# PCB_TrafficLight_-_Copy.net
KiCad netlist of a schematic drawn in Altium Designer
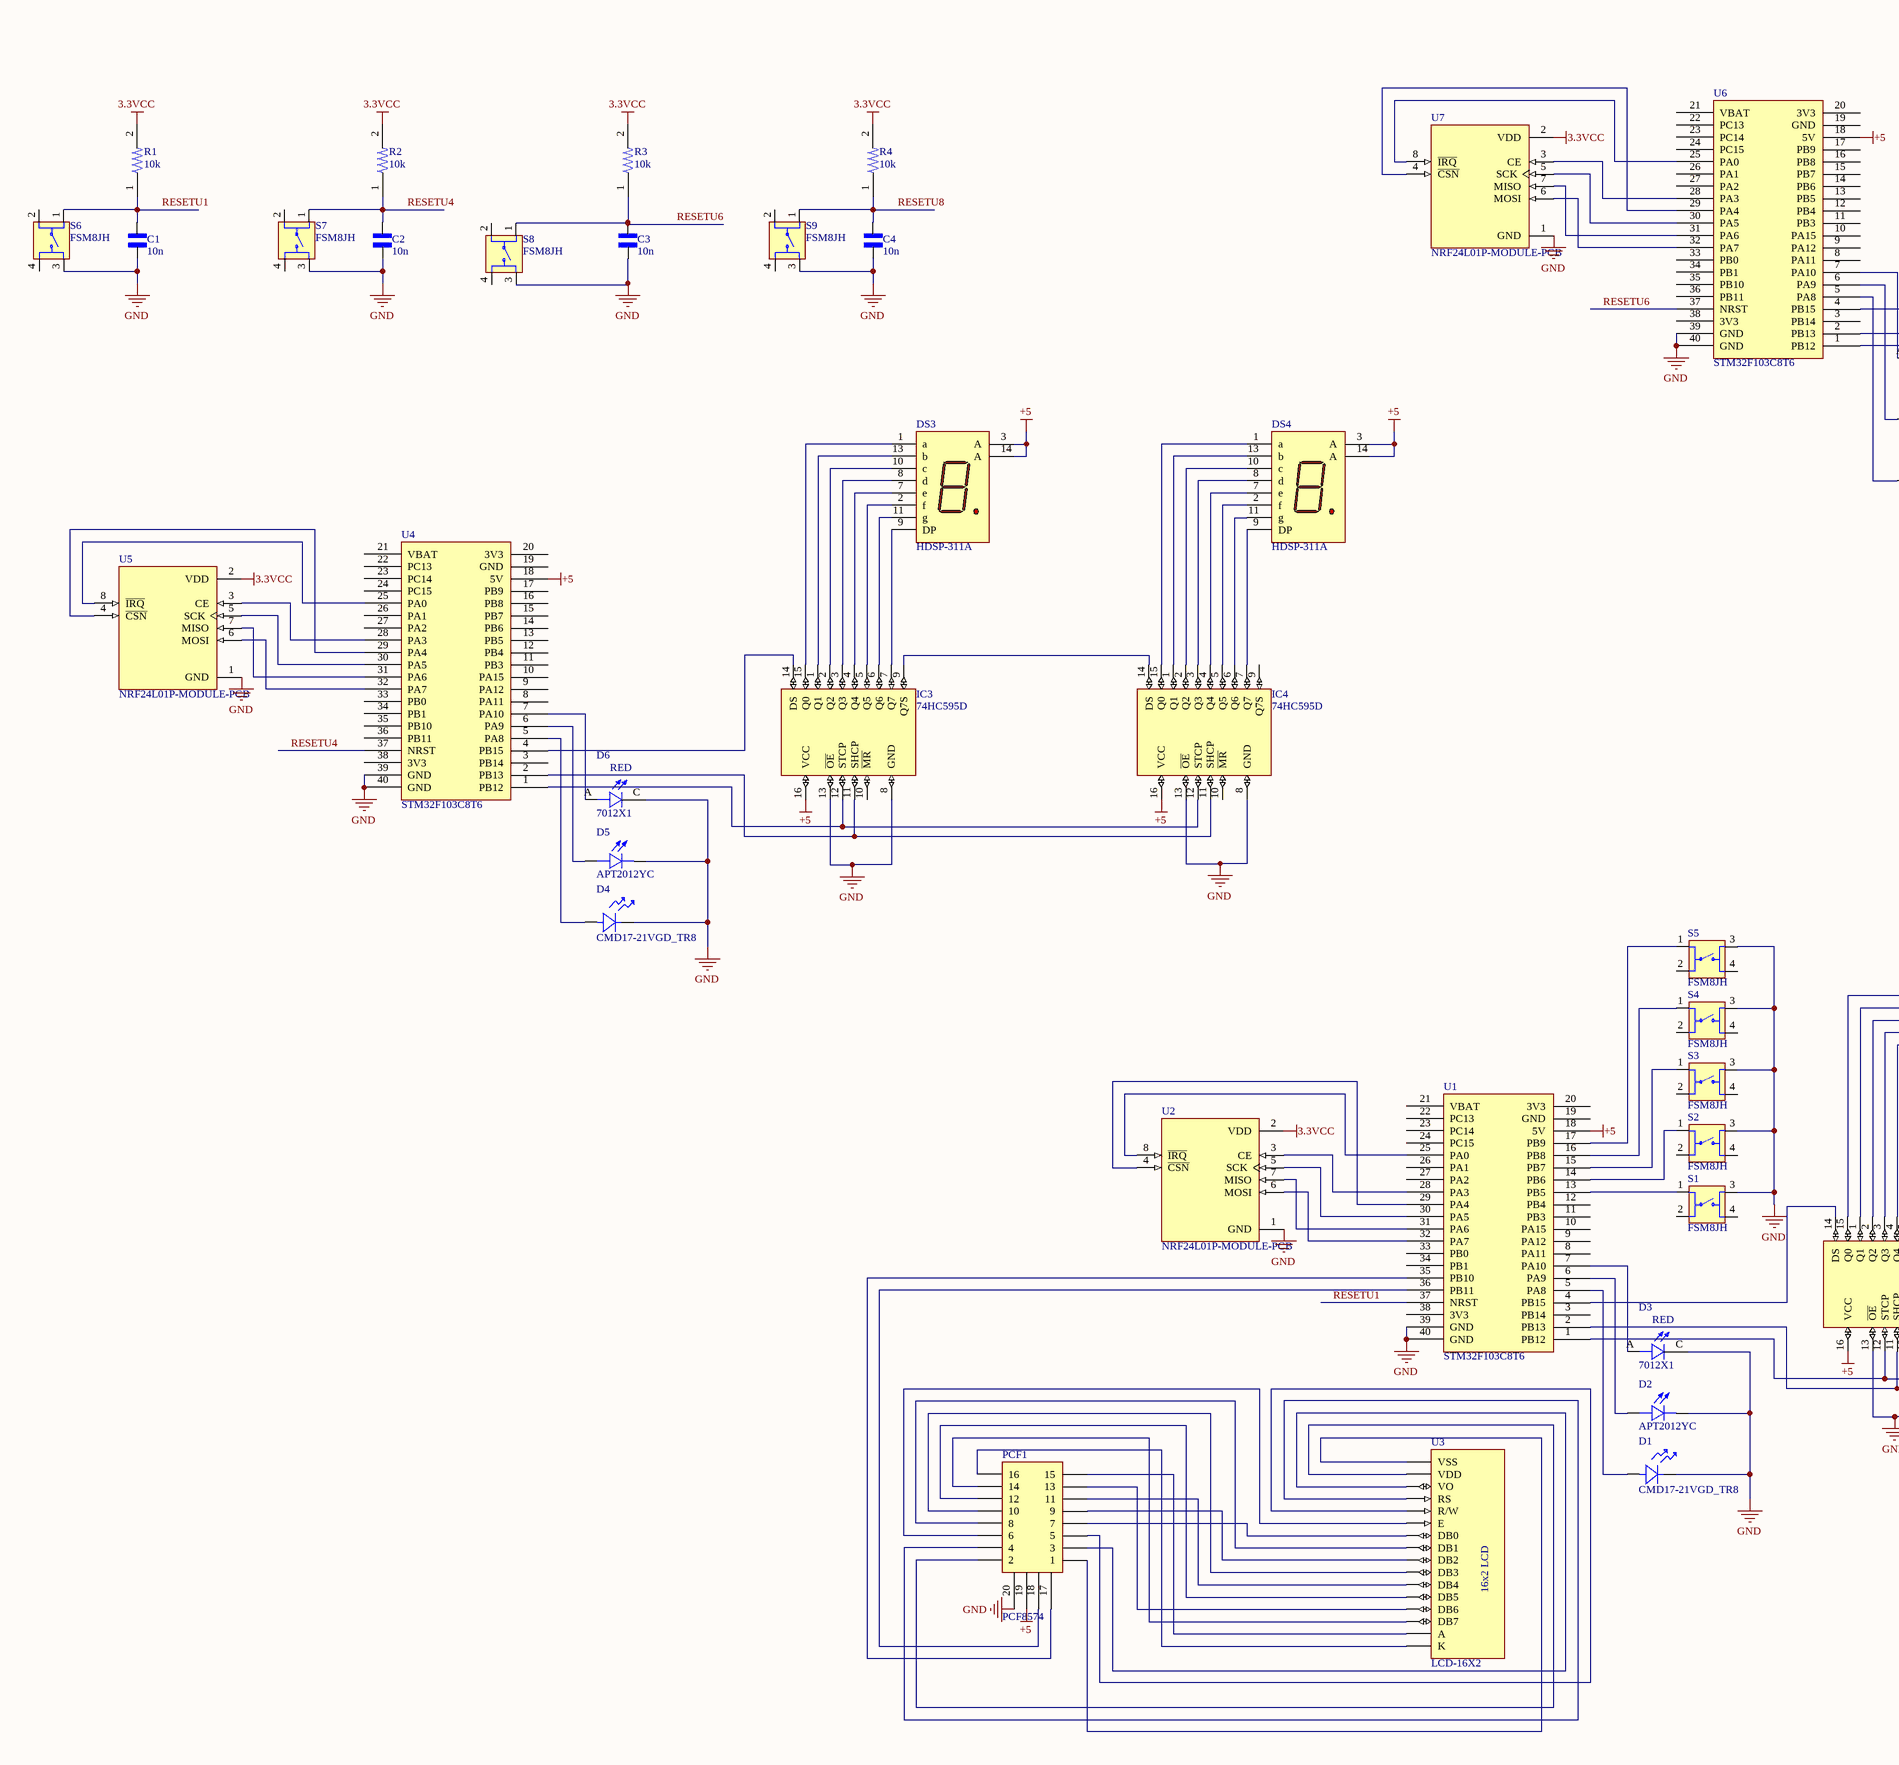
[diagram p0: PCB_TrafficLight - Copy.SchDoc, left]
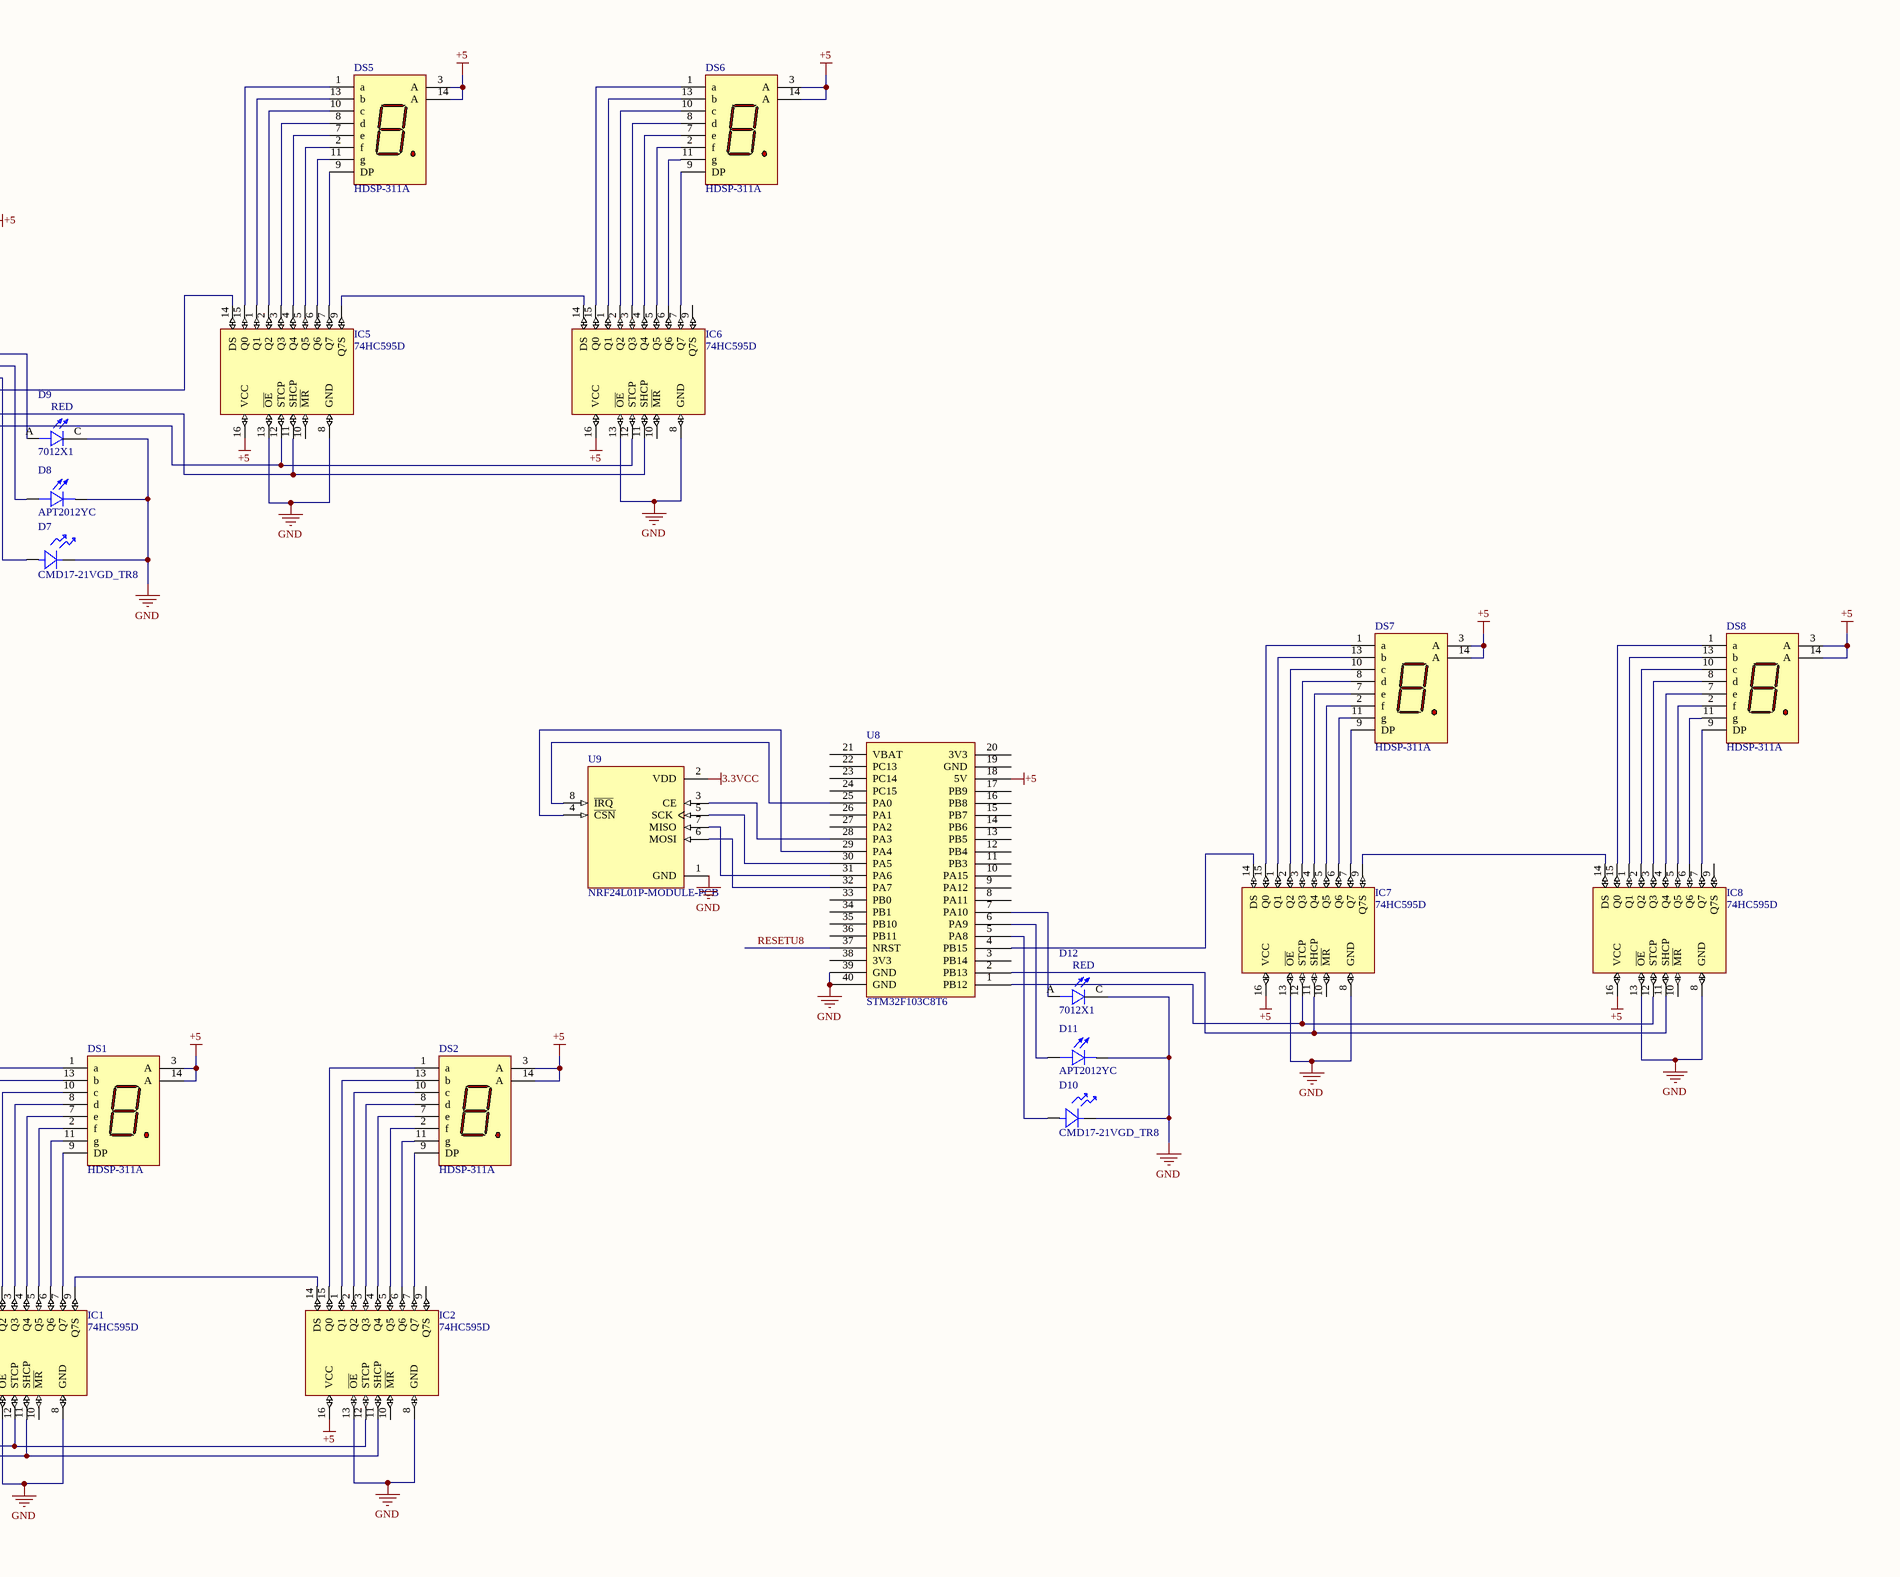
[diagram p1: PCB_TrafficLight - Copy.SchDoc, right]

(export (version "E")
  (design (tool "Eeschema 10.0.6"))
  (components
    (comp (ref "C1")
      (value "10n")
      (footprint "CAPC1005X55N")
      (description "Multilayer Ceramic Capacitors MLCC - SMD/SMT")
      (fields (field (name "MF") "Murata") (field (name "MP") "GCM155R11H103KA40D"))
      (libsource (lib "GCM155R11H103KA40D") (part "GCM155R11H103KA40D"))
    )
    (comp (ref "C2")
      (value "10n")
      (footprint "CAPC1005X55N")
      (description "Multilayer Ceramic Capacitors MLCC - SMD/SMT")
      (fields (field (name "MF") "Murata") (field (name "MP") "GCM155R11H103KA40D"))
      (libsource (lib "GCM155R11H103KA40D") (part "GCM155R11H103KA40D"))
    )
    (comp (ref "C3")
      (value "10n")
      (footprint "CAPC1005X55N")
      (description "Multilayer Ceramic Capacitors MLCC - SMD/SMT")
      (fields (field (name "MF") "Murata") (field (name "MP") "GCM155R11H103KA40D"))
      (libsource (lib "GCM155R11H103KA40D") (part "GCM155R11H103KA40D"))
    )
    (comp (ref "C4")
      (value "10n")
      (footprint "CAPC1005X55N")
      (description "Multilayer Ceramic Capacitors MLCC - SMD/SMT")
      (fields (field (name "MF") "Murata") (field (name "MP") "GCM155R11H103KA40D"))
      (libsource (lib "GCM155R11H103KA40D") (part "GCM155R11H103KA40D"))
    )
    (comp (ref "D1")
      (value "CMD17-21VGD_TR8")
      (footprint "LED_CMD17-21VGD_TR8")
      (description "Green - LED Indication - Discrete 2.1V 0805 (2012 Metric)")
      (fields (field (name "MF") "VCC") (field (name "MP") "CMD17-21VGD/TR8"))
      (libsource (lib "CMD17-21VGD_TR8") (part "CMD17-21VGD_TR8"))
    )
    (comp (ref "D2")
      (value "APT2012YC")
      (footprint "LED_APT2012YC")
      (fields (field (name "MF") "{'manufacturer': u'Kingbright'}"))
      (libsource (lib "APT2012YC") (part "APT2012YC"))
    )
    (comp (ref "D3")
      (value "7012X1")
      (footprint "LED_7012X1")
      (description "Red - LED Indication - Discrete 1.7V 0805 (2012 Metric)")
      (fields (field (name "MF") "VCC"))
      (libsource (lib "7012X1") (part "7012X1"))
    )
    (comp (ref "D4")
      (value "CMD17-21VGD_TR8")
      (footprint "LED_CMD17-21VGD_TR8")
      (description "Green - LED Indication - Discrete 2.1V 0805 (2012 Metric)")
      (fields (field (name "MF") "VCC") (field (name "MP") "CMD17-21VGD/TR8"))
      (libsource (lib "CMD17-21VGD_TR8") (part "CMD17-21VGD_TR8"))
    )
    (comp (ref "D5")
      (value "APT2012YC")
      (footprint "LED_APT2012YC")
      (fields (field (name "MF") "{'manufacturer': u'Kingbright'}"))
      (libsource (lib "APT2012YC") (part "APT2012YC"))
    )
    (comp (ref "D6")
      (value "7012X1")
      (footprint "LED_7012X1")
      (description "Red - LED Indication - Discrete 1.7V 0805 (2012 Metric)")
      (fields (field (name "MF") "VCC"))
      (libsource (lib "7012X1") (part "7012X1"))
    )
    (comp (ref "D7")
      (value "CMD17-21VGD_TR8")
      (footprint "LED_CMD17-21VGD_TR8")
      (description "Green - LED Indication - Discrete 2.1V 0805 (2012 Metric)")
      (fields (field (name "MF") "VCC") (field (name "MP") "CMD17-21VGD/TR8"))
      (libsource (lib "CMD17-21VGD_TR8") (part "CMD17-21VGD_TR8"))
    )
    (comp (ref "D8")
      (value "APT2012YC")
      (footprint "LED_APT2012YC")
      (fields (field (name "MF") "{'manufacturer': u'Kingbright'}"))
      (libsource (lib "APT2012YC") (part "APT2012YC"))
    )
    (comp (ref "D9")
      (value "7012X1")
      (footprint "LED_7012X1")
      (description "Red - LED Indication - Discrete 1.7V 0805 (2012 Metric)")
      (fields (field (name "MF") "VCC"))
      (libsource (lib "7012X1") (part "7012X1"))
    )
    (comp (ref "D10")
      (value "CMD17-21VGD_TR8")
      (footprint "LED_CMD17-21VGD_TR8")
      (description "Green - LED Indication - Discrete 2.1V 0805 (2012 Metric)")
      (fields (field (name "MF") "VCC") (field (name "MP") "CMD17-21VGD/TR8"))
      (libsource (lib "CMD17-21VGD_TR8") (part "CMD17-21VGD_TR8"))
    )
    (comp (ref "D11")
      (value "APT2012YC")
      (footprint "LED_APT2012YC")
      (fields (field (name "MF") "{'manufacturer': u'Kingbright'}"))
      (libsource (lib "APT2012YC") (part "APT2012YC"))
    )
    (comp (ref "D12")
      (value "7012X1")
      (footprint "LED_7012X1")
      (description "Red - LED Indication - Discrete 1.7V 0805 (2012 Metric)")
      (fields (field (name "MF") "VCC"))
      (libsource (lib "7012X1") (part "7012X1"))
    )
    (comp (ref "DS1")
      (value "HDSP-311A")
      (footprint "F-10(14)")
      (description "10.16 mm Single Digit General Purpose AlGaAs Red 7-Segment Display: CA, RH DP")
      (fields (field (name "PUBLISHER") "Altium Limited"))
      (libsource (lib "Agilent LED Display 7-Segment, 1-Digit") (part "HDSP-311A"))
    )
    (comp (ref "DS2")
      (value "HDSP-311A")
      (footprint "F-10(14)")
      (description "10.16 mm Single Digit General Purpose AlGaAs Red 7-Segment Display: CA, RH DP")
      (fields (field (name "PUBLISHER") "Altium Limited"))
      (libsource (lib "Agilent LED Display 7-Segment, 1-Digit") (part "HDSP-311A"))
    )
    (comp (ref "DS3")
      (value "HDSP-311A")
      (footprint "F-10(14)")
      (description "10.16 mm Single Digit General Purpose AlGaAs Red 7-Segment Display: CA, RH DP")
      (fields (field (name "PUBLISHER") "Altium Limited"))
      (libsource (lib "Agilent LED Display 7-Segment, 1-Digit") (part "HDSP-311A"))
    )
    (comp (ref "DS4")
      (value "HDSP-311A")
      (footprint "F-10(14)")
      (description "10.16 mm Single Digit General Purpose AlGaAs Red 7-Segment Display: CA, RH DP")
      (fields (field (name "PUBLISHER") "Altium Limited"))
      (libsource (lib "Agilent LED Display 7-Segment, 1-Digit") (part "HDSP-311A"))
    )
    (comp (ref "DS5")
      (value "HDSP-311A")
      (footprint "F-10(14)")
      (description "10.16 mm Single Digit General Purpose AlGaAs Red 7-Segment Display: CA, RH DP")
      (fields (field (name "PUBLISHER") "Altium Limited"))
      (libsource (lib "Agilent LED Display 7-Segment, 1-Digit") (part "HDSP-311A"))
    )
    (comp (ref "DS6")
      (value "HDSP-311A")
      (footprint "F-10(14)")
      (description "10.16 mm Single Digit General Purpose AlGaAs Red 7-Segment Display: CA, RH DP")
      (fields (field (name "PUBLISHER") "Altium Limited"))
      (libsource (lib "Agilent LED Display 7-Segment, 1-Digit") (part "HDSP-311A"))
    )
    (comp (ref "DS7")
      (value "HDSP-311A")
      (footprint "F-10(14)")
      (description "10.16 mm Single Digit General Purpose AlGaAs Red 7-Segment Display: CA, RH DP")
      (fields (field (name "PUBLISHER") "Altium Limited"))
      (libsource (lib "Agilent LED Display 7-Segment, 1-Digit") (part "HDSP-311A"))
    )
    (comp (ref "DS8")
      (value "HDSP-311A")
      (footprint "F-10(14)")
      (description "10.16 mm Single Digit General Purpose AlGaAs Red 7-Segment Display: CA, RH DP")
      (fields (field (name "PUBLISHER") "Altium Limited"))
      (libsource (lib "Agilent LED Display 7-Segment, 1-Digit") (part "HDSP-311A"))
    )
    (comp (ref "IC1")
      (value "74HC595D")
      (footprint "SOIC127P600X175-16N")
      (description "Shift Register Single 8-Bit Serial to Serial/Parallel 16-Pin SOIC T/R")
      (fields (field (name "MF") "NXP Semiconductors"))
      (libsource (lib "74HC595D") (part "74HC595D"))
    )
    (comp (ref "IC2")
      (value "74HC595D")
      (footprint "SOIC127P600X175-16N")
      (description "Shift Register Single 8-Bit Serial to Serial/Parallel 16-Pin SOIC T/R")
      (fields (field (name "MF") "NXP Semiconductors"))
      (libsource (lib "74HC595D") (part "74HC595D"))
    )
    (comp (ref "IC3")
      (value "74HC595D")
      (footprint "SOIC127P600X175-16N")
      (description "Shift Register Single 8-Bit Serial to Serial/Parallel 16-Pin SOIC T/R")
      (fields (field (name "MF") "NXP Semiconductors"))
      (libsource (lib "74HC595D") (part "74HC595D"))
    )
    (comp (ref "IC4")
      (value "74HC595D")
      (footprint "SOIC127P600X175-16N")
      (description "Shift Register Single 8-Bit Serial to Serial/Parallel 16-Pin SOIC T/R")
      (fields (field (name "MF") "NXP Semiconductors"))
      (libsource (lib "74HC595D") (part "74HC595D"))
    )
    (comp (ref "IC5")
      (value "74HC595D")
      (footprint "SOIC127P600X175-16N")
      (description "Shift Register Single 8-Bit Serial to Serial/Parallel 16-Pin SOIC T/R")
      (fields (field (name "MF") "NXP Semiconductors"))
      (libsource (lib "74HC595D") (part "74HC595D"))
    )
    (comp (ref "IC6")
      (value "74HC595D")
      (footprint "SOIC127P600X175-16N")
      (description "Shift Register Single 8-Bit Serial to Serial/Parallel 16-Pin SOIC T/R")
      (fields (field (name "MF") "NXP Semiconductors"))
      (libsource (lib "74HC595D") (part "74HC595D"))
    )
    (comp (ref "IC7")
      (value "74HC595D")
      (footprint "SOIC127P600X175-16N")
      (description "Shift Register Single 8-Bit Serial to Serial/Parallel 16-Pin SOIC T/R")
      (fields (field (name "MF") "NXP Semiconductors"))
      (libsource (lib "74HC595D") (part "74HC595D"))
    )
    (comp (ref "IC8")
      (value "74HC595D")
      (footprint "SOIC127P600X175-16N")
      (description "Shift Register Single 8-Bit Serial to Serial/Parallel 16-Pin SOIC T/R")
      (fields (field (name "MF") "NXP Semiconductors"))
      (libsource (lib "74HC595D") (part "74HC595D"))
    )
    (comp (ref "PCF1") (value "PCF8574") (footprint "PCF8574") (libsource (lib "PCF8574") (part "PCF8574")))
    (comp (ref "R1")
      (value "10k")
      (footprint "RESC1608X50N_CPF0603F10KC1")
      (description "Res Thin Film 0603 10K Ohm 1% 1/16W Â±50ppm/Â°C Molded SMD SMD Paper T/R")
      (fields (field (name "TOLERANCE") "1%") (field (name "MF") "TE Connectivity"))
      (libsource (lib "CPF0603F10KC1") (part "CPF0603F10KC1"))
    )
    (comp (ref "R2")
      (value "10k")
      (footprint "RESC1608X50N_CPF0603F10KC1")
      (description "Res Thin Film 0603 10K Ohm 1% 1/16W Â±50ppm/Â°C Molded SMD SMD Paper T/R")
      (fields (field (name "TOLERANCE") "1%") (field (name "MF") "TE Connectivity"))
      (libsource (lib "CPF0603F10KC1") (part "CPF0603F10KC1"))
    )
    (comp (ref "R3")
      (value "10k")
      (footprint "RESC1608X50N_CPF0603F10KC1")
      (description "Res Thin Film 0603 10K Ohm 1% 1/16W Â±50ppm/Â°C Molded SMD SMD Paper T/R")
      (fields (field (name "TOLERANCE") "1%") (field (name "MF") "TE Connectivity"))
      (libsource (lib "CPF0603F10KC1") (part "CPF0603F10KC1"))
    )
    (comp (ref "R4")
      (value "10k")
      (footprint "RESC1608X50N_CPF0603F10KC1")
      (description "Res Thin Film 0603 10K Ohm 1% 1/16W Â±50ppm/Â°C Molded SMD SMD Paper T/R")
      (fields (field (name "TOLERANCE") "1%") (field (name "MF") "TE Connectivity"))
      (libsource (lib "CPF0603F10KC1") (part "CPF0603F10KC1"))
    )
    (comp (ref "S1")
      (value "FSM8JH")
      (footprint "SW_FSM8JH")
      (description "Tactile Switch SPST-NO Top Actuated Through Hole")
      (fields (field (name "MF") "TE Connectivity"))
      (libsource (lib "FSM8JH") (part "FSM8JH"))
    )
    (comp (ref "S2")
      (value "FSM8JH")
      (footprint "SW_FSM8JH")
      (description "Tactile Switch SPST-NO Top Actuated Through Hole")
      (fields (field (name "MF") "TE Connectivity"))
      (libsource (lib "FSM8JH") (part "FSM8JH"))
    )
    (comp (ref "S3")
      (value "FSM8JH")
      (footprint "SW_FSM8JH")
      (description "Tactile Switch SPST-NO Top Actuated Through Hole")
      (fields (field (name "MF") "TE Connectivity"))
      (libsource (lib "FSM8JH") (part "FSM8JH"))
    )
    (comp (ref "S4")
      (value "FSM8JH")
      (footprint "SW_FSM8JH")
      (description "Tactile Switch SPST-NO Top Actuated Through Hole")
      (fields (field (name "MF") "TE Connectivity"))
      (libsource (lib "FSM8JH") (part "FSM8JH"))
    )
    (comp (ref "S5")
      (value "FSM8JH")
      (footprint "SW_FSM8JH")
      (description "Tactile Switch SPST-NO Top Actuated Through Hole")
      (fields (field (name "MF") "TE Connectivity"))
      (libsource (lib "FSM8JH") (part "FSM8JH"))
    )
    (comp (ref "S6")
      (value "FSM8JH")
      (footprint "SW_FSM8JH")
      (description "Tactile Switch SPST-NO Top Actuated Through Hole")
      (fields (field (name "MF") "TE Connectivity"))
      (libsource (lib "") (part "FSM8JH_1"))
    )
    (comp (ref "S7")
      (value "FSM8JH")
      (footprint "SW_FSM8JH")
      (description "Tactile Switch SPST-NO Top Actuated Through Hole")
      (fields (field (name "MF") "TE Connectivity"))
      (libsource (lib "") (part "FSM8JH_1"))
    )
    (comp (ref "S8")
      (value "FSM8JH")
      (footprint "SW_FSM8JH")
      (description "Tactile Switch SPST-NO Top Actuated Through Hole")
      (fields (field (name "MF") "TE Connectivity"))
      (libsource (lib "") (part "FSM8JH_1"))
    )
    (comp (ref "S9")
      (value "FSM8JH")
      (footprint "SW_FSM8JH")
      (description "Tactile Switch SPST-NO Top Actuated Through Hole")
      (fields (field (name "MF") "TE Connectivity"))
      (libsource (lib "") (part "FSM8JH_1"))
    )
    (comp (ref "U1")
      (value "STM32F103C8T6")
      (footprint "Stm32 BluePill")
      (description "Designed By @Alixahedi")
      (libsource (lib "Stm32 Blue Pill") (part "BluePill"))
    )
    (comp (ref "U2")
      (value "NRF24L01P-MODULE-PCB")
      (footprint "XCVR_NRF24L01P-MODULE-PCB")
      (description "- Transceiver For Use With nRF24L01+")
      (fields (field (name "MF") "Nordic Semiconductor"))
      (libsource (lib "NRF24L01P-MODULE-PCB") (part "NRF24L01P-MODULE-PCB"))
    )
    (comp (ref "U3")
      (value "LCD-16X2")
      (footprint "MODULE_LCD-16X2")
      (description "Display Development Tools 16x2 Black on Green Char LCD w Backlight")
      (fields (field (name "MF") "Gravitech"))
      (libsource (lib "LCD-16X2") (part "LCD-16X2"))
    )
    (comp (ref "U4")
      (value "STM32F103C8T6")
      (footprint "Stm32 BluePill")
      (description "Designed By @Alixahedi")
      (libsource (lib "Stm32 Blue Pill") (part "BluePill"))
    )
    (comp (ref "U5")
      (value "NRF24L01P-MODULE-PCB")
      (footprint "XCVR_NRF24L01P-MODULE-PCB")
      (description "- Transceiver For Use With nRF24L01+")
      (fields (field (name "MF") "Nordic Semiconductor"))
      (libsource (lib "NRF24L01P-MODULE-PCB") (part "NRF24L01P-MODULE-PCB"))
    )
    (comp (ref "U6")
      (value "STM32F103C8T6")
      (footprint "Stm32 BluePill")
      (description "Designed By @Alixahedi")
      (libsource (lib "Stm32 Blue Pill") (part "BluePill"))
    )
    (comp (ref "U7")
      (value "NRF24L01P-MODULE-PCB")
      (footprint "XCVR_NRF24L01P-MODULE-PCB")
      (description "- Transceiver For Use With nRF24L01+")
      (fields (field (name "MF") "Nordic Semiconductor"))
      (libsource (lib "NRF24L01P-MODULE-PCB") (part "NRF24L01P-MODULE-PCB"))
    )
    (comp (ref "U8")
      (value "STM32F103C8T6")
      (footprint "Stm32 BluePill")
      (description "Designed By @Alixahedi")
      (libsource (lib "Stm32 Blue Pill") (part "BluePill"))
    )
    (comp (ref "U9")
      (value "NRF24L01P-MODULE-PCB")
      (footprint "XCVR_NRF24L01P-MODULE-PCB")
      (description "- Transceiver For Use With nRF24L01+")
      (fields (field (name "MF") "Nordic Semiconductor"))
      (libsource (lib "NRF24L01P-MODULE-PCB") (part "NRF24L01P-MODULE-PCB"))
    )
  )
  (nets
    (net (code "1") (name "+5") (class "Default")
      (node (ref "DS1") (pin "14") (pinfunction "A_14") (pintype "passive"))
      (node (ref "DS1") (pin "3") (pinfunction "A_3") (pintype "passive"))
      (node (ref "DS2") (pin "14") (pinfunction "A_14") (pintype "passive"))
      (node (ref "DS2") (pin "3") (pinfunction "A_3") (pintype "passive"))
      (node (ref "DS3") (pin "14") (pinfunction "A_14") (pintype "passive"))
      (node (ref "DS3") (pin "3") (pinfunction "A_3") (pintype "passive"))
      (node (ref "DS4") (pin "14") (pinfunction "A_14") (pintype "passive"))
      (node (ref "DS4") (pin "3") (pinfunction "A_3") (pintype "passive"))
      (node (ref "DS5") (pin "14") (pinfunction "A_14") (pintype "passive"))
      (node (ref "DS5") (pin "3") (pinfunction "A_3") (pintype "passive"))
      (node (ref "DS6") (pin "14") (pinfunction "A_14") (pintype "passive"))
      (node (ref "DS6") (pin "3") (pinfunction "A_3") (pintype "passive"))
      (node (ref "DS7") (pin "14") (pinfunction "A_14") (pintype "passive"))
      (node (ref "DS7") (pin "3") (pinfunction "A_3") (pintype "passive"))
      (node (ref "DS8") (pin "14") (pinfunction "A_14") (pintype "passive"))
      (node (ref "DS8") (pin "3") (pinfunction "A_3") (pintype "passive"))
      (node (ref "IC1") (pin "16") (pinfunction "VCC_16") (pintype "bidirectional"))
      (node (ref "IC2") (pin "16") (pinfunction "VCC_16") (pintype "bidirectional"))
      (node (ref "IC3") (pin "16") (pinfunction "VCC_16") (pintype "bidirectional"))
      (node (ref "IC4") (pin "16") (pinfunction "VCC_16") (pintype "bidirectional"))
      (node (ref "IC5") (pin "16") (pinfunction "VCC_16") (pintype "bidirectional"))
      (node (ref "IC6") (pin "16") (pinfunction "VCC_16") (pintype "bidirectional"))
      (node (ref "IC7") (pin "16") (pinfunction "VCC_16") (pintype "bidirectional"))
      (node (ref "IC8") (pin "16") (pinfunction "VCC_16") (pintype "bidirectional"))
      (node (ref "PCF1") (pin "19") (pinfunction "19_19") (pintype "passive"))
      (node (ref "U1") (pin "18") (pinfunction "5V_18") (pintype "passive"))
      (node (ref "U4") (pin "18") (pinfunction "5V_18") (pintype "passive"))
      (node (ref "U6") (pin "18") (pinfunction "5V_18") (pintype "passive"))
      (node (ref "U8") (pin "18") (pinfunction "5V_18") (pintype "passive"))
    )
    (net (code "2") (name "/RESETU1") (class "Default")
      (node (ref "C1") (pin "2") (pinfunction "2_2") (pintype "passive"))
      (node (ref "R1") (pin "1") (pinfunction "1_1") (pintype "passive"))
      (node (ref "S6") (pin "1") (pinfunction "1_1") (pintype "passive"))
      (node (ref "U1") (pin "37") (pinfunction "NRST_37") (pintype "passive"))
    )
    (net (code "3") (name "/RESETU4") (class "Default")
      (node (ref "C2") (pin "2") (pinfunction "2_2") (pintype "passive"))
      (node (ref "R2") (pin "1") (pinfunction "1_1") (pintype "passive"))
      (node (ref "S7") (pin "1") (pinfunction "1_1") (pintype "passive"))
      (node (ref "U4") (pin "37") (pinfunction "NRST_37") (pintype "passive"))
    )
    (net (code "4") (name "/RESETU6") (class "Default")
      (node (ref "C3") (pin "2") (pinfunction "2_2") (pintype "passive"))
      (node (ref "R3") (pin "1") (pinfunction "1_1") (pintype "passive"))
      (node (ref "S8") (pin "1") (pinfunction "1_1") (pintype "passive"))
      (node (ref "U6") (pin "37") (pinfunction "NRST_37") (pintype "passive"))
    )
    (net (code "5") (name "/RESETU8") (class "Default")
      (node (ref "C4") (pin "2") (pinfunction "2_2") (pintype "passive"))
      (node (ref "R4") (pin "1") (pinfunction "1_1") (pintype "passive"))
      (node (ref "S9") (pin "1") (pinfunction "1_1") (pintype "passive"))
      (node (ref "U8") (pin "37") (pinfunction "NRST_37") (pintype "passive"))
    )
    (net (code "6") (name "3.3VCC") (class "Default")
      (node (ref "R1") (pin "2") (pinfunction "2_2") (pintype "passive"))
      (node (ref "R2") (pin "2") (pinfunction "2_2") (pintype "passive"))
      (node (ref "R3") (pin "2") (pinfunction "2_2") (pintype "passive"))
      (node (ref "R4") (pin "2") (pinfunction "2_2") (pintype "passive"))
      (node (ref "U2") (pin "2") (pinfunction "VDD_2") (pintype "power_in"))
      (node (ref "U5") (pin "2") (pinfunction "VDD_2") (pintype "power_in"))
      (node (ref "U7") (pin "2") (pinfunction "VDD_2") (pintype "power_in"))
      (node (ref "U9") (pin "2") (pinfunction "VDD_2") (pintype "power_in"))
    )
    (net (code "7") (name "GND") (class "Default")
      (node (ref "C1") (pin "1") (pinfunction "1_1") (pintype "passive"))
      (node (ref "C2") (pin "1") (pinfunction "1_1") (pintype "passive"))
      (node (ref "C3") (pin "1") (pinfunction "1_1") (pintype "passive"))
      (node (ref "C4") (pin "1") (pinfunction "1_1") (pintype "passive"))
      (node (ref "D1") (pin "2") (pinfunction "2_2") (pintype "passive"))
      (node (ref "D10") (pin "2") (pinfunction "2_2") (pintype "passive"))
      (node (ref "D11") (pin "1") (pinfunction "C_1") (pintype "passive"))
      (node (ref "D12") (pin "C") (pinfunction "C_C") (pintype "passive"))
      (node (ref "D2") (pin "1") (pinfunction "C_1") (pintype "passive"))
      (node (ref "D3") (pin "C") (pinfunction "C_C") (pintype "passive"))
      (node (ref "D4") (pin "2") (pinfunction "2_2") (pintype "passive"))
      (node (ref "D5") (pin "1") (pinfunction "C_1") (pintype "passive"))
      (node (ref "D6") (pin "C") (pinfunction "C_C") (pintype "passive"))
      (node (ref "D7") (pin "2") (pinfunction "2_2") (pintype "passive"))
      (node (ref "D8") (pin "1") (pinfunction "C_1") (pintype "passive"))
      (node (ref "D9") (pin "C") (pinfunction "C_C") (pintype "passive"))
      (node (ref "IC1") (pin "13") (pinfunction "~{OE}_13") (pintype "bidirectional"))
      (node (ref "IC1") (pin "8") (pinfunction "GND_8") (pintype "bidirectional"))
      (node (ref "IC2") (pin "13") (pinfunction "~{OE}_13") (pintype "bidirectional"))
      (node (ref "IC2") (pin "8") (pinfunction "GND_8") (pintype "bidirectional"))
      (node (ref "IC3") (pin "13") (pinfunction "~{OE}_13") (pintype "bidirectional"))
      (node (ref "IC3") (pin "8") (pinfunction "GND_8") (pintype "bidirectional"))
      (node (ref "IC4") (pin "13") (pinfunction "~{OE}_13") (pintype "bidirectional"))
      (node (ref "IC4") (pin "8") (pinfunction "GND_8") (pintype "bidirectional"))
      (node (ref "IC5") (pin "13") (pinfunction "~{OE}_13") (pintype "bidirectional"))
      (node (ref "IC5") (pin "8") (pinfunction "GND_8") (pintype "bidirectional"))
      (node (ref "IC6") (pin "13") (pinfunction "~{OE}_13") (pintype "bidirectional"))
      (node (ref "IC6") (pin "8") (pinfunction "GND_8") (pintype "bidirectional"))
      (node (ref "IC7") (pin "13") (pinfunction "~{OE}_13") (pintype "bidirectional"))
      (node (ref "IC7") (pin "8") (pinfunction "GND_8") (pintype "bidirectional"))
      (node (ref "IC8") (pin "13") (pinfunction "~{OE}_13") (pintype "bidirectional"))
      (node (ref "IC8") (pin "8") (pinfunction "GND_8") (pintype "bidirectional"))
      (node (ref "PCF1") (pin "20") (pinfunction "20_20") (pintype "passive"))
      (node (ref "S1") (pin "3") (pinfunction "3_3") (pintype "passive"))
      (node (ref "S2") (pin "3") (pinfunction "3_3") (pintype "passive"))
      (node (ref "S3") (pin "3") (pinfunction "3_3") (pintype "passive"))
      (node (ref "S4") (pin "3") (pinfunction "3_3") (pintype "passive"))
      (node (ref "S5") (pin "3") (pinfunction "3_3") (pintype "passive"))
      (node (ref "S6") (pin "3") (pinfunction "3_3") (pintype "passive"))
      (node (ref "S7") (pin "3") (pinfunction "3_3") (pintype "passive"))
      (node (ref "S8") (pin "3") (pinfunction "3_3") (pintype "passive"))
      (node (ref "S9") (pin "3") (pinfunction "3_3") (pintype "passive"))
      (node (ref "U1") (pin "39") (pinfunction "GND_39") (pintype "passive"))
      (node (ref "U1") (pin "40") (pinfunction "GND_40") (pintype "passive"))
      (node (ref "U2") (pin "1") (pinfunction "GND_1") (pintype "power_in"))
      (node (ref "U4") (pin "39") (pinfunction "GND_39") (pintype "passive"))
      (node (ref "U4") (pin "40") (pinfunction "GND_40") (pintype "passive"))
      (node (ref "U5") (pin "1") (pinfunction "GND_1") (pintype "power_in"))
      (node (ref "U6") (pin "39") (pinfunction "GND_39") (pintype "passive"))
      (node (ref "U6") (pin "40") (pinfunction "GND_40") (pintype "passive"))
      (node (ref "U7") (pin "1") (pinfunction "GND_1") (pintype "power_in"))
      (node (ref "U8") (pin "39") (pinfunction "GND_39") (pintype "passive"))
      (node (ref "U8") (pin "40") (pinfunction "GND_40") (pintype "passive"))
      (node (ref "U9") (pin "1") (pinfunction "GND_1") (pintype "power_in"))
    )
    (net (code "8") (name "Net-(D2-A)") (class "Default")
      (node (ref "D2") (pin "2") (pinfunction "A_2") (pintype "passive"))
      (node (ref "U1") (pin "6") (pinfunction "PA9_6") (pintype "passive"))
    )
    (net (code "9") (name "Net-(D5-A)") (class "Default")
      (node (ref "D5") (pin "2") (pinfunction "A_2") (pintype "passive"))
      (node (ref "U4") (pin "6") (pinfunction "PA9_6") (pintype "passive"))
    )
    (net (code "10") (name "Net-(D8-A)") (class "Default")
      (node (ref "D8") (pin "2") (pinfunction "A_2") (pintype "passive"))
      (node (ref "U6") (pin "6") (pinfunction "PA9_6") (pintype "passive"))
    )
    (net (code "11") (name "Net-(D11-A)") (class "Default")
      (node (ref "D11") (pin "2") (pinfunction "A_2") (pintype "passive"))
      (node (ref "U8") (pin "6") (pinfunction "PA9_6") (pintype "passive"))
    )
    (net (code "12") (name "Net-(DS1-DP)") (class "Default")
      (node (ref "DS1") (pin "9") (pinfunction "DP_9") (pintype "passive"))
      (node (ref "IC1") (pin "7") (pinfunction "Q7_7") (pintype "bidirectional"))
    )
    (net (code "13") (name "Net-(DS1-a)") (class "Default")
      (node (ref "DS1") (pin "1") (pinfunction "a_1") (pintype "passive"))
      (node (ref "IC1") (pin "15") (pinfunction "Q0_15") (pintype "bidirectional"))
    )
    (net (code "14") (name "Net-(DS1-b)") (class "Default")
      (node (ref "DS1") (pin "13") (pinfunction "b_13") (pintype "passive"))
      (node (ref "IC1") (pin "1") (pinfunction "Q1_1") (pintype "bidirectional"))
    )
    (net (code "15") (name "Net-(DS1-c)") (class "Default")
      (node (ref "DS1") (pin "10") (pinfunction "c_10") (pintype "passive"))
      (node (ref "IC1") (pin "2") (pinfunction "Q2_2") (pintype "bidirectional"))
    )
    (net (code "16") (name "Net-(DS1-d)") (class "Default")
      (node (ref "DS1") (pin "8") (pinfunction "d_8") (pintype "passive"))
      (node (ref "IC1") (pin "3") (pinfunction "Q3_3") (pintype "bidirectional"))
    )
    (net (code "17") (name "Net-(DS1-e)") (class "Default")
      (node (ref "DS1") (pin "7") (pinfunction "e_7") (pintype "passive"))
      (node (ref "IC1") (pin "4") (pinfunction "Q4_4") (pintype "bidirectional"))
    )
    (net (code "18") (name "Net-(DS1-f)") (class "Default")
      (node (ref "DS1") (pin "2") (pinfunction "f_2") (pintype "passive"))
      (node (ref "IC1") (pin "5") (pinfunction "Q5_5") (pintype "bidirectional"))
    )
    (net (code "19") (name "Net-(DS1-g)") (class "Default")
      (node (ref "DS1") (pin "11") (pinfunction "g_11") (pintype "passive"))
      (node (ref "IC1") (pin "6") (pinfunction "Q6_6") (pintype "bidirectional"))
    )
    (net (code "20") (name "Net-(DS2-DP)") (class "Default")
      (node (ref "DS2") (pin "9") (pinfunction "DP_9") (pintype "passive"))
      (node (ref "IC2") (pin "7") (pinfunction "Q7_7") (pintype "bidirectional"))
    )
    (net (code "21") (name "Net-(DS2-a)") (class "Default")
      (node (ref "DS2") (pin "1") (pinfunction "a_1") (pintype "passive"))
      (node (ref "IC2") (pin "15") (pinfunction "Q0_15") (pintype "bidirectional"))
    )
    (net (code "22") (name "Net-(DS2-b)") (class "Default")
      (node (ref "DS2") (pin "13") (pinfunction "b_13") (pintype "passive"))
      (node (ref "IC2") (pin "1") (pinfunction "Q1_1") (pintype "bidirectional"))
    )
    (net (code "23") (name "Net-(DS2-c)") (class "Default")
      (node (ref "DS2") (pin "10") (pinfunction "c_10") (pintype "passive"))
      (node (ref "IC2") (pin "2") (pinfunction "Q2_2") (pintype "bidirectional"))
    )
    (net (code "24") (name "Net-(DS2-d)") (class "Default")
      (node (ref "DS2") (pin "8") (pinfunction "d_8") (pintype "passive"))
      (node (ref "IC2") (pin "3") (pinfunction "Q3_3") (pintype "bidirectional"))
    )
    (net (code "25") (name "Net-(DS2-e)") (class "Default")
      (node (ref "DS2") (pin "7") (pinfunction "e_7") (pintype "passive"))
      (node (ref "IC2") (pin "4") (pinfunction "Q4_4") (pintype "bidirectional"))
    )
    (net (code "26") (name "Net-(DS2-f)") (class "Default")
      (node (ref "DS2") (pin "2") (pinfunction "f_2") (pintype "passive"))
      (node (ref "IC2") (pin "5") (pinfunction "Q5_5") (pintype "bidirectional"))
    )
    (net (code "27") (name "Net-(DS2-g)") (class "Default")
      (node (ref "DS2") (pin "11") (pinfunction "g_11") (pintype "passive"))
      (node (ref "IC2") (pin "6") (pinfunction "Q6_6") (pintype "bidirectional"))
    )
    (net (code "28") (name "Net-(DS3-DP)") (class "Default")
      (node (ref "DS3") (pin "9") (pinfunction "DP_9") (pintype "passive"))
      (node (ref "IC3") (pin "7") (pinfunction "Q7_7") (pintype "bidirectional"))
    )
    (net (code "29") (name "Net-(DS3-a)") (class "Default")
      (node (ref "DS3") (pin "1") (pinfunction "a_1") (pintype "passive"))
      (node (ref "IC3") (pin "15") (pinfunction "Q0_15") (pintype "bidirectional"))
    )
    (net (code "30") (name "Net-(DS3-b)") (class "Default")
      (node (ref "DS3") (pin "13") (pinfunction "b_13") (pintype "passive"))
      (node (ref "IC3") (pin "1") (pinfunction "Q1_1") (pintype "bidirectional"))
    )
    (net (code "31") (name "Net-(DS3-c)") (class "Default")
      (node (ref "DS3") (pin "10") (pinfunction "c_10") (pintype "passive"))
      (node (ref "IC3") (pin "2") (pinfunction "Q2_2") (pintype "bidirectional"))
    )
    (net (code "32") (name "Net-(DS3-d)") (class "Default")
      (node (ref "DS3") (pin "8") (pinfunction "d_8") (pintype "passive"))
      (node (ref "IC3") (pin "3") (pinfunction "Q3_3") (pintype "bidirectional"))
    )
    (net (code "33") (name "Net-(DS3-e)") (class "Default")
      (node (ref "DS3") (pin "7") (pinfunction "e_7") (pintype "passive"))
      (node (ref "IC3") (pin "4") (pinfunction "Q4_4") (pintype "bidirectional"))
    )
    (net (code "34") (name "Net-(DS3-f)") (class "Default")
      (node (ref "DS3") (pin "2") (pinfunction "f_2") (pintype "passive"))
      (node (ref "IC3") (pin "5") (pinfunction "Q5_5") (pintype "bidirectional"))
    )
    (net (code "35") (name "Net-(DS3-g)") (class "Default")
      (node (ref "DS3") (pin "11") (pinfunction "g_11") (pintype "passive"))
      (node (ref "IC3") (pin "6") (pinfunction "Q6_6") (pintype "bidirectional"))
    )
    (net (code "36") (name "Net-(DS4-DP)") (class "Default")
      (node (ref "DS4") (pin "9") (pinfunction "DP_9") (pintype "passive"))
      (node (ref "IC4") (pin "7") (pinfunction "Q7_7") (pintype "bidirectional"))
    )
    (net (code "37") (name "Net-(DS4-a)") (class "Default")
      (node (ref "DS4") (pin "1") (pinfunction "a_1") (pintype "passive"))
      (node (ref "IC4") (pin "15") (pinfunction "Q0_15") (pintype "bidirectional"))
    )
    (net (code "38") (name "Net-(DS4-b)") (class "Default")
      (node (ref "DS4") (pin "13") (pinfunction "b_13") (pintype "passive"))
      (node (ref "IC4") (pin "1") (pinfunction "Q1_1") (pintype "bidirectional"))
    )
    (net (code "39") (name "Net-(DS4-c)") (class "Default")
      (node (ref "DS4") (pin "10") (pinfunction "c_10") (pintype "passive"))
      (node (ref "IC4") (pin "2") (pinfunction "Q2_2") (pintype "bidirectional"))
    )
    (net (code "40") (name "Net-(DS4-d)") (class "Default")
      (node (ref "DS4") (pin "8") (pinfunction "d_8") (pintype "passive"))
      (node (ref "IC4") (pin "3") (pinfunction "Q3_3") (pintype "bidirectional"))
    )
    (net (code "41") (name "Net-(DS4-e)") (class "Default")
      (node (ref "DS4") (pin "7") (pinfunction "e_7") (pintype "passive"))
      (node (ref "IC4") (pin "4") (pinfunction "Q4_4") (pintype "bidirectional"))
    )
    (net (code "42") (name "Net-(DS4-f)") (class "Default")
      (node (ref "DS4") (pin "2") (pinfunction "f_2") (pintype "passive"))
      (node (ref "IC4") (pin "5") (pinfunction "Q5_5") (pintype "bidirectional"))
    )
    (net (code "43") (name "Net-(DS4-g)") (class "Default")
      (node (ref "DS4") (pin "11") (pinfunction "g_11") (pintype "passive"))
      (node (ref "IC4") (pin "6") (pinfunction "Q6_6") (pintype "bidirectional"))
    )
    (net (code "44") (name "Net-(DS5-DP)") (class "Default")
      (node (ref "DS5") (pin "9") (pinfunction "DP_9") (pintype "passive"))
      (node (ref "IC5") (pin "7") (pinfunction "Q7_7") (pintype "bidirectional"))
    )
    (net (code "45") (name "Net-(DS5-a)") (class "Default")
      (node (ref "DS5") (pin "1") (pinfunction "a_1") (pintype "passive"))
      (node (ref "IC5") (pin "15") (pinfunction "Q0_15") (pintype "bidirectional"))
    )
    (net (code "46") (name "Net-(DS5-b)") (class "Default")
      (node (ref "DS5") (pin "13") (pinfunction "b_13") (pintype "passive"))
      (node (ref "IC5") (pin "1") (pinfunction "Q1_1") (pintype "bidirectional"))
    )
    (net (code "47") (name "Net-(DS5-c)") (class "Default")
      (node (ref "DS5") (pin "10") (pinfunction "c_10") (pintype "passive"))
      (node (ref "IC5") (pin "2") (pinfunction "Q2_2") (pintype "bidirectional"))
    )
    (net (code "48") (name "Net-(DS5-d)") (class "Default")
      (node (ref "DS5") (pin "8") (pinfunction "d_8") (pintype "passive"))
      (node (ref "IC5") (pin "3") (pinfunction "Q3_3") (pintype "bidirectional"))
    )
    (net (code "49") (name "Net-(DS5-e)") (class "Default")
      (node (ref "DS5") (pin "7") (pinfunction "e_7") (pintype "passive"))
      (node (ref "IC5") (pin "4") (pinfunction "Q4_4") (pintype "bidirectional"))
    )
    (net (code "50") (name "Net-(DS5-f)") (class "Default")
      (node (ref "DS5") (pin "2") (pinfunction "f_2") (pintype "passive"))
      (node (ref "IC5") (pin "5") (pinfunction "Q5_5") (pintype "bidirectional"))
    )
    (net (code "51") (name "Net-(DS5-g)") (class "Default")
      (node (ref "DS5") (pin "11") (pinfunction "g_11") (pintype "passive"))
      (node (ref "IC5") (pin "6") (pinfunction "Q6_6") (pintype "bidirectional"))
    )
    (net (code "52") (name "Net-(DS6-DP)") (class "Default")
      (node (ref "DS6") (pin "9") (pinfunction "DP_9") (pintype "passive"))
      (node (ref "IC6") (pin "7") (pinfunction "Q7_7") (pintype "bidirectional"))
    )
    (net (code "53") (name "Net-(DS6-a)") (class "Default")
      (node (ref "DS6") (pin "1") (pinfunction "a_1") (pintype "passive"))
      (node (ref "IC6") (pin "15") (pinfunction "Q0_15") (pintype "bidirectional"))
    )
    (net (code "54") (name "Net-(DS6-b)") (class "Default")
      (node (ref "DS6") (pin "13") (pinfunction "b_13") (pintype "passive"))
      (node (ref "IC6") (pin "1") (pinfunction "Q1_1") (pintype "bidirectional"))
    )
    (net (code "55") (name "Net-(DS6-c)") (class "Default")
      (node (ref "DS6") (pin "10") (pinfunction "c_10") (pintype "passive"))
      (node (ref "IC6") (pin "2") (pinfunction "Q2_2") (pintype "bidirectional"))
    )
    (net (code "56") (name "Net-(DS6-d)") (class "Default")
      (node (ref "DS6") (pin "8") (pinfunction "d_8") (pintype "passive"))
      (node (ref "IC6") (pin "3") (pinfunction "Q3_3") (pintype "bidirectional"))
    )
    (net (code "57") (name "Net-(DS6-e)") (class "Default")
      (node (ref "DS6") (pin "7") (pinfunction "e_7") (pintype "passive"))
      (node (ref "IC6") (pin "4") (pinfunction "Q4_4") (pintype "bidirectional"))
    )
    (net (code "58") (name "Net-(DS6-f)") (class "Default")
      (node (ref "DS6") (pin "2") (pinfunction "f_2") (pintype "passive"))
      (node (ref "IC6") (pin "5") (pinfunction "Q5_5") (pintype "bidirectional"))
    )
    (net (code "59") (name "Net-(DS6-g)") (class "Default")
      (node (ref "DS6") (pin "11") (pinfunction "g_11") (pintype "passive"))
      (node (ref "IC6") (pin "6") (pinfunction "Q6_6") (pintype "bidirectional"))
    )
    (net (code "60") (name "Net-(DS7-DP)") (class "Default")
      (node (ref "DS7") (pin "9") (pinfunction "DP_9") (pintype "passive"))
      (node (ref "IC7") (pin "7") (pinfunction "Q7_7") (pintype "bidirectional"))
    )
    (net (code "61") (name "Net-(DS7-a)") (class "Default")
      (node (ref "DS7") (pin "1") (pinfunction "a_1") (pintype "passive"))
      (node (ref "IC7") (pin "15") (pinfunction "Q0_15") (pintype "bidirectional"))
    )
    (net (code "62") (name "Net-(DS7-b)") (class "Default")
      (node (ref "DS7") (pin "13") (pinfunction "b_13") (pintype "passive"))
      (node (ref "IC7") (pin "1") (pinfunction "Q1_1") (pintype "bidirectional"))
    )
    (net (code "63") (name "Net-(DS7-c)") (class "Default")
      (node (ref "DS7") (pin "10") (pinfunction "c_10") (pintype "passive"))
      (node (ref "IC7") (pin "2") (pinfunction "Q2_2") (pintype "bidirectional"))
    )
    (net (code "64") (name "Net-(DS7-d)") (class "Default")
      (node (ref "DS7") (pin "8") (pinfunction "d_8") (pintype "passive"))
      (node (ref "IC7") (pin "3") (pinfunction "Q3_3") (pintype "bidirectional"))
    )
    (net (code "65") (name "Net-(DS7-e)") (class "Default")
      (node (ref "DS7") (pin "7") (pinfunction "e_7") (pintype "passive"))
      (node (ref "IC7") (pin "4") (pinfunction "Q4_4") (pintype "bidirectional"))
    )
    (net (code "66") (name "Net-(DS7-f)") (class "Default")
      (node (ref "DS7") (pin "2") (pinfunction "f_2") (pintype "passive"))
      (node (ref "IC7") (pin "5") (pinfunction "Q5_5") (pintype "bidirectional"))
    )
    (net (code "67") (name "Net-(DS7-g)") (class "Default")
      (node (ref "DS7") (pin "11") (pinfunction "g_11") (pintype "passive"))
      (node (ref "IC7") (pin "6") (pinfunction "Q6_6") (pintype "bidirectional"))
    )
    (net (code "68") (name "Net-(DS8-DP)") (class "Default")
      (node (ref "DS8") (pin "9") (pinfunction "DP_9") (pintype "passive"))
      (node (ref "IC8") (pin "7") (pinfunction "Q7_7") (pintype "bidirectional"))
    )
    (net (code "69") (name "Net-(DS8-a)") (class "Default")
      (node (ref "DS8") (pin "1") (pinfunction "a_1") (pintype "passive"))
      (node (ref "IC8") (pin "15") (pinfunction "Q0_15") (pintype "bidirectional"))
    )
    (net (code "70") (name "Net-(DS8-b)") (class "Default")
      (node (ref "DS8") (pin "13") (pinfunction "b_13") (pintype "passive"))
      (node (ref "IC8") (pin "1") (pinfunction "Q1_1") (pintype "bidirectional"))
    )
    (net (code "71") (name "Net-(DS8-c)") (class "Default")
      (node (ref "DS8") (pin "10") (pinfunction "c_10") (pintype "passive"))
      (node (ref "IC8") (pin "2") (pinfunction "Q2_2") (pintype "bidirectional"))
    )
    (net (code "72") (name "Net-(DS8-d)") (class "Default")
      (node (ref "DS8") (pin "8") (pinfunction "d_8") (pintype "passive"))
      (node (ref "IC8") (pin "3") (pinfunction "Q3_3") (pintype "bidirectional"))
    )
    (net (code "73") (name "Net-(DS8-e)") (class "Default")
      (node (ref "DS8") (pin "7") (pinfunction "e_7") (pintype "passive"))
      (node (ref "IC8") (pin "4") (pinfunction "Q4_4") (pintype "bidirectional"))
    )
    (net (code "74") (name "Net-(DS8-f)") (class "Default")
      (node (ref "DS8") (pin "2") (pinfunction "f_2") (pintype "passive"))
      (node (ref "IC8") (pin "5") (pinfunction "Q5_5") (pintype "bidirectional"))
    )
    (net (code "75") (name "Net-(DS8-g)") (class "Default")
      (node (ref "DS8") (pin "11") (pinfunction "g_11") (pintype "passive"))
      (node (ref "IC8") (pin "6") (pinfunction "Q6_6") (pintype "bidirectional"))
    )
    (net (code "76") (name "Net-(IC1-DS)") (class "Default")
      (node (ref "IC1") (pin "14") (pinfunction "DS_14") (pintype "bidirectional"))
      (node (ref "U1") (pin "4") (pinfunction "PB15_4") (pintype "passive"))
    )
    (net (code "77") (name "Net-(IC1-Q7S)") (class "Default")
      (node (ref "IC1") (pin "9") (pinfunction "Q7S_9") (pintype "bidirectional"))
      (node (ref "IC2") (pin "14") (pinfunction "DS_14") (pintype "bidirectional"))
    )
    (net (code "78") (name "Net-(IC1-SHCP)") (class "Default")
      (node (ref "IC1") (pin "11") (pinfunction "SHCP_11") (pintype "bidirectional"))
      (node (ref "IC2") (pin "11") (pinfunction "SHCP_11") (pintype "bidirectional"))
      (node (ref "U1") (pin "2") (pinfunction "PB13_2") (pintype "passive"))
    )
    (net (code "79") (name "Net-(IC1-STCP)") (class "Default")
      (node (ref "IC1") (pin "12") (pinfunction "STCP_12") (pintype "bidirectional"))
      (node (ref "IC2") (pin "12") (pinfunction "STCP_12") (pintype "bidirectional"))
      (node (ref "U1") (pin "1") (pinfunction "PB12_1") (pintype "passive"))
    )
    (net (code "80") (name "Net-(IC3-DS)") (class "Default")
      (node (ref "IC3") (pin "14") (pinfunction "DS_14") (pintype "bidirectional"))
      (node (ref "U4") (pin "4") (pinfunction "PB15_4") (pintype "passive"))
    )
    (net (code "81") (name "Net-(IC3-Q7S)") (class "Default")
      (node (ref "IC3") (pin "9") (pinfunction "Q7S_9") (pintype "bidirectional"))
      (node (ref "IC4") (pin "14") (pinfunction "DS_14") (pintype "bidirectional"))
    )
    (net (code "82") (name "Net-(IC3-SHCP)") (class "Default")
      (node (ref "IC3") (pin "11") (pinfunction "SHCP_11") (pintype "bidirectional"))
      (node (ref "IC4") (pin "11") (pinfunction "SHCP_11") (pintype "bidirectional"))
      (node (ref "U4") (pin "2") (pinfunction "PB13_2") (pintype "passive"))
    )
    (net (code "83") (name "Net-(IC3-STCP)") (class "Default")
      (node (ref "IC3") (pin "12") (pinfunction "STCP_12") (pintype "bidirectional"))
      (node (ref "IC4") (pin "12") (pinfunction "STCP_12") (pintype "bidirectional"))
      (node (ref "U4") (pin "1") (pinfunction "PB12_1") (pintype "passive"))
    )
    (net (code "84") (name "Net-(IC5-DS)") (class "Default")
      (node (ref "IC5") (pin "14") (pinfunction "DS_14") (pintype "bidirectional"))
      (node (ref "U6") (pin "4") (pinfunction "PB15_4") (pintype "passive"))
    )
    (net (code "85") (name "Net-(IC5-Q7S)") (class "Default")
      (node (ref "IC5") (pin "9") (pinfunction "Q7S_9") (pintype "bidirectional"))
      (node (ref "IC6") (pin "14") (pinfunction "DS_14") (pintype "bidirectional"))
    )
    (net (code "86") (name "Net-(IC5-SHCP)") (class "Default")
      (node (ref "IC5") (pin "11") (pinfunction "SHCP_11") (pintype "bidirectional"))
      (node (ref "IC6") (pin "11") (pinfunction "SHCP_11") (pintype "bidirectional"))
      (node (ref "U6") (pin "2") (pinfunction "PB13_2") (pintype "passive"))
    )
    (net (code "87") (name "Net-(IC5-STCP)") (class "Default")
      (node (ref "IC5") (pin "12") (pinfunction "STCP_12") (pintype "bidirectional"))
      (node (ref "IC6") (pin "12") (pinfunction "STCP_12") (pintype "bidirectional"))
      (node (ref "U6") (pin "1") (pinfunction "PB12_1") (pintype "passive"))
    )
    (net (code "88") (name "Net-(IC7-DS)") (class "Default")
      (node (ref "IC7") (pin "14") (pinfunction "DS_14") (pintype "bidirectional"))
      (node (ref "U8") (pin "4") (pinfunction "PB15_4") (pintype "passive"))
    )
    (net (code "89") (name "Net-(IC7-Q7S)") (class "Default")
      (node (ref "IC7") (pin "9") (pinfunction "Q7S_9") (pintype "bidirectional"))
      (node (ref "IC8") (pin "14") (pinfunction "DS_14") (pintype "bidirectional"))
    )
    (net (code "90") (name "Net-(IC7-SHCP)") (class "Default")
      (node (ref "IC7") (pin "11") (pinfunction "SHCP_11") (pintype "bidirectional"))
      (node (ref "IC8") (pin "11") (pinfunction "SHCP_11") (pintype "bidirectional"))
      (node (ref "U8") (pin "2") (pinfunction "PB13_2") (pintype "passive"))
    )
    (net (code "91") (name "Net-(IC7-STCP)") (class "Default")
      (node (ref "IC7") (pin "12") (pinfunction "STCP_12") (pintype "bidirectional"))
      (node (ref "IC8") (pin "12") (pinfunction "STCP_12") (pintype "bidirectional"))
      (node (ref "U8") (pin "1") (pinfunction "PB12_1") (pintype "passive"))
    )
    (net (code "92") (name "Net-(U1-PA0)") (class "Default")
      (node (ref "U1") (pin "25") (pinfunction "PA0_25") (pintype "passive"))
      (node (ref "U2") (pin "8") (pinfunction "~{IRQ}_8") (pintype "input"))
    )
    (net (code "93") (name "Net-(U1-PA3)") (class "Default")
      (node (ref "U1") (pin "28") (pinfunction "PA3_28") (pintype "passive"))
      (node (ref "U2") (pin "3") (pinfunction "CE_3") (pintype "input"))
    )
    (net (code "94") (name "Net-(U1-PA4)") (class "Default")
      (node (ref "U1") (pin "29") (pinfunction "PA4_29") (pintype "passive"))
      (node (ref "U2") (pin "4") (pinfunction "~{CSN}_4") (pintype "input"))
    )
    (net (code "95") (name "Net-(U1-PA5)") (class "Default")
      (node (ref "U1") (pin "30") (pinfunction "PA5_30") (pintype "passive"))
      (node (ref "U2") (pin "5") (pinfunction "SCK_5") (pintype "input"))
    )
    (net (code "96") (name "Net-(U1-PA6)") (class "Default")
      (node (ref "U1") (pin "31") (pinfunction "PA6_31") (pintype "passive"))
      (node (ref "U2") (pin "7") (pinfunction "MISO_7") (pintype "input"))
    )
    (net (code "97") (name "Net-(U1-PA7)") (class "Default")
      (node (ref "U1") (pin "32") (pinfunction "PA7_32") (pintype "passive"))
      (node (ref "U2") (pin "6") (pinfunction "MOSI_6") (pintype "input"))
    )
    (net (code "98") (name "Net-(U1-PA8)") (class "Default")
      (node (ref "D1") (pin "1") (pinfunction "1_1") (pintype "passive"))
      (node (ref "U1") (pin "5") (pinfunction "PA8_5") (pintype "passive"))
    )
    (net (code "99") (name "Net-(U1-PA10)") (class "Default")
      (node (ref "D3") (pin "A") (pinfunction "A_A") (pintype "passive"))
      (node (ref "U1") (pin "7") (pinfunction "PA10_7") (pintype "passive"))
    )
    (net (code "100") (name "Net-(U1-PB5)") (class "Default")
      (node (ref "S1") (pin "1") (pinfunction "1_1") (pintype "passive"))
      (node (ref "U1") (pin "13") (pinfunction "PB5_13") (pintype "passive"))
    )
    (net (code "101") (name "Net-(U1-PB6)") (class "Default")
      (node (ref "S2") (pin "1") (pinfunction "1_1") (pintype "passive"))
      (node (ref "U1") (pin "14") (pinfunction "PB6_14") (pintype "passive"))
    )
    (net (code "102") (name "Net-(U1-PB7)") (class "Default")
      (node (ref "S3") (pin "1") (pinfunction "1_1") (pintype "passive"))
      (node (ref "U1") (pin "15") (pinfunction "PB7_15") (pintype "passive"))
    )
    (net (code "103") (name "Net-(U1-PB8)") (class "Default")
      (node (ref "S4") (pin "1") (pinfunction "1_1") (pintype "passive"))
      (node (ref "U1") (pin "16") (pinfunction "PB8_16") (pintype "passive"))
    )
    (net (code "104") (name "Net-(U1-PB9)") (class "Default")
      (node (ref "S5") (pin "1") (pinfunction "1_1") (pintype "passive"))
      (node (ref "U1") (pin "17") (pinfunction "PB9_17") (pintype "passive"))
    )
    (net (code "105") (name "Net-(U1-PB10)") (class "Default")
      (node (ref "PCF1") (pin "17") (pinfunction "17_17") (pintype "passive"))
      (node (ref "U1") (pin "35") (pinfunction "PB10_35") (pintype "passive"))
    )
    (net (code "106") (name "Net-(U1-PB11)") (class "Default")
      (node (ref "PCF1") (pin "18") (pinfunction "18_18") (pintype "passive"))
      (node (ref "U1") (pin "36") (pinfunction "PB11_36") (pintype "passive"))
    )
    (net (code "107") (name "Net-(U3-A)") (class "Default")
      (node (ref "PCF1") (pin "15") (pinfunction "15_15") (pintype "passive"))
      (node (ref "U3") (pin "15") (pinfunction "A_15") (pintype "power_in"))
    )
    (net (code "108") (name "Net-(U3-DB0)") (class "Default")
      (node (ref "PCF1") (pin "7") (pinfunction "7_7") (pintype "passive"))
      (node (ref "U3") (pin "7") (pinfunction "DB0_7") (pintype "bidirectional"))
    )
    (net (code "109") (name "Net-(U3-DB1)") (class "Default")
      (node (ref "PCF1") (pin "8") (pinfunction "8_8") (pintype "passive"))
      (node (ref "U3") (pin "8") (pinfunction "DB1_8") (pintype "bidirectional"))
    )
    (net (code "110") (name "Net-(U3-DB2)") (class "Default")
      (node (ref "PCF1") (pin "9") (pinfunction "9_9") (pintype "passive"))
      (node (ref "U3") (pin "9") (pinfunction "DB2_9") (pintype "bidirectional"))
    )
    (net (code "111") (name "Net-(U3-DB3)") (class "Default")
      (node (ref "PCF1") (pin "10") (pinfunction "10_10") (pintype "passive"))
      (node (ref "U3") (pin "10") (pinfunction "DB3_10") (pintype "bidirectional"))
    )
    (net (code "112") (name "Net-(U3-DB4)") (class "Default")
      (node (ref "PCF1") (pin "11") (pinfunction "11_11") (pintype "passive"))
      (node (ref "U3") (pin "11") (pinfunction "DB4_11") (pintype "bidirectional"))
    )
    (net (code "113") (name "Net-(U3-DB5)") (class "Default")
      (node (ref "PCF1") (pin "12") (pinfunction "12_12") (pintype "passive"))
      (node (ref "U3") (pin "12") (pinfunction "DB5_12") (pintype "bidirectional"))
    )
    (net (code "114") (name "Net-(U3-DB6)") (class "Default")
      (node (ref "PCF1") (pin "13") (pinfunction "13_13") (pintype "passive"))
      (node (ref "U3") (pin "13") (pinfunction "DB6_13") (pintype "bidirectional"))
    )
    (net (code "115") (name "Net-(U3-DB7)") (class "Default")
      (node (ref "PCF1") (pin "14") (pinfunction "14_14") (pintype "passive"))
      (node (ref "U3") (pin "14") (pinfunction "DB7_14") (pintype "bidirectional"))
    )
    (net (code "116") (name "Net-(U3-E)") (class "Default")
      (node (ref "PCF1") (pin "6") (pinfunction "6_6") (pintype "passive"))
      (node (ref "U3") (pin "6") (pinfunction "E_6") (pintype "input"))
    )
    (net (code "117") (name "Net-(U3-K)") (class "Default")
      (node (ref "PCF1") (pin "16") (pinfunction "16_16") (pintype "passive"))
      (node (ref "U3") (pin "16") (pinfunction "K_16") (pintype "power_in"))
    )
    (net (code "118") (name "Net-(U3-RS)") (class "Default")
      (node (ref "PCF1") (pin "4") (pinfunction "4_4") (pintype "passive"))
      (node (ref "U3") (pin "4") (pinfunction "RS_4") (pintype "input"))
    )
    (net (code "119") (name "Net-(U3-R{slash}W)") (class "Default")
      (node (ref "PCF1") (pin "5") (pinfunction "5_5") (pintype "passive"))
      (node (ref "U3") (pin "5") (pinfunction "R/W_5") (pintype "input"))
    )
    (net (code "120") (name "Net-(U3-VDD)") (class "Default")
      (node (ref "PCF1") (pin "2") (pinfunction "2_2") (pintype "passive"))
      (node (ref "U3") (pin "2") (pinfunction "VDD_2") (pintype "power_in"))
    )
    (net (code "121") (name "Net-(U3-VO)") (class "Default")
      (node (ref "PCF1") (pin "3") (pinfunction "3_3") (pintype "passive"))
      (node (ref "U3") (pin "3") (pinfunction "VO_3") (pintype "bidirectional"))
    )
    (net (code "122") (name "Net-(U3-VSS)") (class "Default")
      (node (ref "PCF1") (pin "1") (pinfunction "1_1") (pintype "passive"))
      (node (ref "U3") (pin "1") (pinfunction "VSS_1") (pintype "power_in"))
    )
    (net (code "123") (name "Net-(U4-PA0)") (class "Default")
      (node (ref "U4") (pin "25") (pinfunction "PA0_25") (pintype "passive"))
      (node (ref "U5") (pin "8") (pinfunction "~{IRQ}_8") (pintype "input"))
    )
    (net (code "124") (name "Net-(U4-PA3)") (class "Default")
      (node (ref "U4") (pin "28") (pinfunction "PA3_28") (pintype "passive"))
      (node (ref "U5") (pin "3") (pinfunction "CE_3") (pintype "input"))
    )
    (net (code "125") (name "Net-(U4-PA4)") (class "Default")
      (node (ref "U4") (pin "29") (pinfunction "PA4_29") (pintype "passive"))
      (node (ref "U5") (pin "4") (pinfunction "~{CSN}_4") (pintype "input"))
    )
    (net (code "126") (name "Net-(U4-PA5)") (class "Default")
      (node (ref "U4") (pin "30") (pinfunction "PA5_30") (pintype "passive"))
      (node (ref "U5") (pin "5") (pinfunction "SCK_5") (pintype "input"))
    )
    (net (code "127") (name "Net-(U4-PA6)") (class "Default")
      (node (ref "U4") (pin "31") (pinfunction "PA6_31") (pintype "passive"))
      (node (ref "U5") (pin "7") (pinfunction "MISO_7") (pintype "input"))
    )
    (net (code "128") (name "Net-(U4-PA7)") (class "Default")
      (node (ref "U4") (pin "32") (pinfunction "PA7_32") (pintype "passive"))
      (node (ref "U5") (pin "6") (pinfunction "MOSI_6") (pintype "input"))
    )
    (net (code "129") (name "Net-(U4-PA8)") (class "Default")
      (node (ref "D4") (pin "1") (pinfunction "1_1") (pintype "passive"))
      (node (ref "U4") (pin "5") (pinfunction "PA8_5") (pintype "passive"))
    )
    (net (code "130") (name "Net-(U4-PA10)") (class "Default")
      (node (ref "D6") (pin "A") (pinfunction "A_A") (pintype "passive"))
      (node (ref "U4") (pin "7") (pinfunction "PA10_7") (pintype "passive"))
    )
    (net (code "131") (name "Net-(U6-PA0)") (class "Default")
      (node (ref "U6") (pin "25") (pinfunction "PA0_25") (pintype "passive"))
      (node (ref "U7") (pin "8") (pinfunction "~{IRQ}_8") (pintype "input"))
    )
    (net (code "132") (name "Net-(U6-PA3)") (class "Default")
      (node (ref "U6") (pin "28") (pinfunction "PA3_28") (pintype "passive"))
      (node (ref "U7") (pin "3") (pinfunction "CE_3") (pintype "input"))
    )
    (net (code "133") (name "Net-(U6-PA4)") (class "Default")
      (node (ref "U6") (pin "29") (pinfunction "PA4_29") (pintype "passive"))
      (node (ref "U7") (pin "4") (pinfunction "~{CSN}_4") (pintype "input"))
    )
    (net (code "134") (name "Net-(U6-PA5)") (class "Default")
      (node (ref "U6") (pin "30") (pinfunction "PA5_30") (pintype "passive"))
      (node (ref "U7") (pin "5") (pinfunction "SCK_5") (pintype "input"))
    )
    (net (code "135") (name "Net-(U6-PA6)") (class "Default")
      (node (ref "U6") (pin "31") (pinfunction "PA6_31") (pintype "passive"))
      (node (ref "U7") (pin "7") (pinfunction "MISO_7") (pintype "input"))
    )
    (net (code "136") (name "Net-(U6-PA7)") (class "Default")
      (node (ref "U6") (pin "32") (pinfunction "PA7_32") (pintype "passive"))
      (node (ref "U7") (pin "6") (pinfunction "MOSI_6") (pintype "input"))
    )
    (net (code "137") (name "Net-(U6-PA8)") (class "Default")
      (node (ref "D7") (pin "1") (pinfunction "1_1") (pintype "passive"))
      (node (ref "U6") (pin "5") (pinfunction "PA8_5") (pintype "passive"))
    )
    (net (code "138") (name "Net-(U6-PA10)") (class "Default")
      (node (ref "D9") (pin "A") (pinfunction "A_A") (pintype "passive"))
      (node (ref "U6") (pin "7") (pinfunction "PA10_7") (pintype "passive"))
    )
    (net (code "139") (name "Net-(U8-PA0)") (class "Default")
      (node (ref "U8") (pin "25") (pinfunction "PA0_25") (pintype "passive"))
      (node (ref "U9") (pin "8") (pinfunction "~{IRQ}_8") (pintype "input"))
    )
    (net (code "140") (name "Net-(U8-PA3)") (class "Default")
      (node (ref "U8") (pin "28") (pinfunction "PA3_28") (pintype "passive"))
      (node (ref "U9") (pin "3") (pinfunction "CE_3") (pintype "input"))
    )
    (net (code "141") (name "Net-(U8-PA4)") (class "Default")
      (node (ref "U8") (pin "29") (pinfunction "PA4_29") (pintype "passive"))
      (node (ref "U9") (pin "4") (pinfunction "~{CSN}_4") (pintype "input"))
    )
    (net (code "142") (name "Net-(U8-PA5)") (class "Default")
      (node (ref "U8") (pin "30") (pinfunction "PA5_30") (pintype "passive"))
      (node (ref "U9") (pin "5") (pinfunction "SCK_5") (pintype "input"))
    )
    (net (code "143") (name "Net-(U8-PA6)") (class "Default")
      (node (ref "U8") (pin "31") (pinfunction "PA6_31") (pintype "passive"))
      (node (ref "U9") (pin "7") (pinfunction "MISO_7") (pintype "input"))
    )
    (net (code "144") (name "Net-(U8-PA7)") (class "Default")
      (node (ref "U8") (pin "32") (pinfunction "PA7_32") (pintype "passive"))
      (node (ref "U9") (pin "6") (pinfunction "MOSI_6") (pintype "input"))
    )
    (net (code "145") (name "Net-(U8-PA8)") (class "Default")
      (node (ref "D10") (pin "1") (pinfunction "1_1") (pintype "passive"))
      (node (ref "U8") (pin "5") (pinfunction "PA8_5") (pintype "passive"))
    )
    (net (code "146") (name "Net-(U8-PA10)") (class "Default")
      (node (ref "D12") (pin "A") (pinfunction "A_A") (pintype "passive"))
      (node (ref "U8") (pin "7") (pinfunction "PA10_7") (pintype "passive"))
    )
    (net (code "147") (name "unconnected-(IC1-~{MR}-Pad10)") (class "Default")
      (node (ref "IC1") (pin "10") (pinfunction "~{MR}_10") (pintype "bidirectional"))
    )
    (net (code "148") (name "unconnected-(IC2-Q7S-Pad9)") (class "Default")
      (node (ref "IC2") (pin "9") (pinfunction "Q7S_9") (pintype "bidirectional"))
    )
    (net (code "149") (name "unconnected-(IC2-~{MR}-Pad10)") (class "Default")
      (node (ref "IC2") (pin "10") (pinfunction "~{MR}_10") (pintype "bidirectional"))
    )
    (net (code "150") (name "unconnected-(IC3-~{MR}-Pad10)") (class "Default")
      (node (ref "IC3") (pin "10") (pinfunction "~{MR}_10") (pintype "bidirectional"))
    )
    (net (code "151") (name "unconnected-(IC4-Q7S-Pad9)") (class "Default")
      (node (ref "IC4") (pin "9") (pinfunction "Q7S_9") (pintype "bidirectional"))
    )
    (net (code "152") (name "unconnected-(IC4-~{MR}-Pad10)") (class "Default")
      (node (ref "IC4") (pin "10") (pinfunction "~{MR}_10") (pintype "bidirectional"))
    )
    (net (code "153") (name "unconnected-(IC5-~{MR}-Pad10)") (class "Default")
      (node (ref "IC5") (pin "10") (pinfunction "~{MR}_10") (pintype "bidirectional"))
    )
    (net (code "154") (name "unconnected-(IC6-Q7S-Pad9)") (class "Default")
      (node (ref "IC6") (pin "9") (pinfunction "Q7S_9") (pintype "bidirectional"))
    )
    (net (code "155") (name "unconnected-(IC6-~{MR}-Pad10)") (class "Default")
      (node (ref "IC6") (pin "10") (pinfunction "~{MR}_10") (pintype "bidirectional"))
    )
    (net (code "156") (name "unconnected-(IC7-~{MR}-Pad10)") (class "Default")
      (node (ref "IC7") (pin "10") (pinfunction "~{MR}_10") (pintype "bidirectional"))
    )
    (net (code "157") (name "unconnected-(IC8-Q7S-Pad9)") (class "Default")
      (node (ref "IC8") (pin "9") (pinfunction "Q7S_9") (pintype "bidirectional"))
    )
    (net (code "158") (name "unconnected-(IC8-~{MR}-Pad10)") (class "Default")
      (node (ref "IC8") (pin "10") (pinfunction "~{MR}_10") (pintype "bidirectional"))
    )
    (net (code "159") (name "unconnected-(S1-Pad2)") (class "Default")
      (node (ref "S1") (pin "2") (pinfunction "2_2") (pintype "passive"))
    )
    (net (code "160") (name "unconnected-(S1-Pad4)") (class "Default")
      (node (ref "S1") (pin "4") (pinfunction "4_4") (pintype "passive"))
    )
    (net (code "161") (name "unconnected-(S2-Pad2)") (class "Default")
      (node (ref "S2") (pin "2") (pinfunction "2_2") (pintype "passive"))
    )
    (net (code "162") (name "unconnected-(S2-Pad4)") (class "Default")
      (node (ref "S2") (pin "4") (pinfunction "4_4") (pintype "passive"))
    )
    (net (code "163") (name "unconnected-(S3-Pad2)") (class "Default")
      (node (ref "S3") (pin "2") (pinfunction "2_2") (pintype "passive"))
    )
    (net (code "164") (name "unconnected-(S3-Pad4)") (class "Default")
      (node (ref "S3") (pin "4") (pinfunction "4_4") (pintype "passive"))
    )
    (net (code "165") (name "unconnected-(S4-Pad2)") (class "Default")
      (node (ref "S4") (pin "2") (pinfunction "2_2") (pintype "passive"))
    )
    (net (code "166") (name "unconnected-(S4-Pad4)") (class "Default")
      (node (ref "S4") (pin "4") (pinfunction "4_4") (pintype "passive"))
    )
    (net (code "167") (name "unconnected-(S5-Pad2)") (class "Default")
      (node (ref "S5") (pin "2") (pinfunction "2_2") (pintype "passive"))
    )
    (net (code "168") (name "unconnected-(S5-Pad4)") (class "Default")
      (node (ref "S5") (pin "4") (pinfunction "4_4") (pintype "passive"))
    )
    (net (code "169") (name "unconnected-(S6-Pad2)") (class "Default")
      (node (ref "S6") (pin "2") (pinfunction "2_2") (pintype "passive"))
    )
    (net (code "170") (name "unconnected-(S6-Pad4)") (class "Default")
      (node (ref "S6") (pin "4") (pinfunction "4_4") (pintype "passive"))
    )
    (net (code "171") (name "unconnected-(S7-Pad2)") (class "Default")
      (node (ref "S7") (pin "2") (pinfunction "2_2") (pintype "passive"))
    )
    (net (code "172") (name "unconnected-(S7-Pad4)") (class "Default")
      (node (ref "S7") (pin "4") (pinfunction "4_4") (pintype "passive"))
    )
    (net (code "173") (name "unconnected-(S8-Pad2)") (class "Default")
      (node (ref "S8") (pin "2") (pinfunction "2_2") (pintype "passive"))
    )
    (net (code "174") (name "unconnected-(S8-Pad4)") (class "Default")
      (node (ref "S8") (pin "4") (pinfunction "4_4") (pintype "passive"))
    )
    (net (code "175") (name "unconnected-(S9-Pad2)") (class "Default")
      (node (ref "S9") (pin "2") (pinfunction "2_2") (pintype "passive"))
    )
    (net (code "176") (name "unconnected-(S9-Pad4)") (class "Default")
      (node (ref "S9") (pin "4") (pinfunction "4_4") (pintype "passive"))
    )
    (net (code "177") (name "unconnected-(U1-3V3-Pad20)") (class "Default")
      (node (ref "U1") (pin "20") (pinfunction "3V3_20") (pintype "passive"))
    )
    (net (code "178") (name "unconnected-(U1-3V3-Pad38)") (class "Default")
      (node (ref "U1") (pin "38") (pinfunction "3V3_38") (pintype "passive"))
    )
    (net (code "179") (name "unconnected-(U1-GND-Pad19)") (class "Default")
      (node (ref "U1") (pin "19") (pinfunction "GND_19") (pintype "passive"))
    )
    (net (code "180") (name "unconnected-(U1-PA1-Pad26)") (class "Default")
      (node (ref "U1") (pin "26") (pinfunction "PA1_26") (pintype "passive"))
    )
    (net (code "181") (name "unconnected-(U1-PA2-Pad27)") (class "Default")
      (node (ref "U1") (pin "27") (pinfunction "PA2_27") (pintype "passive"))
    )
    (net (code "182") (name "unconnected-(U1-PA11-Pad8)") (class "Default")
      (node (ref "U1") (pin "8") (pinfunction "PA11_8") (pintype "passive"))
    )
    (net (code "183") (name "unconnected-(U1-PA12-Pad9)") (class "Default")
      (node (ref "U1") (pin "9") (pinfunction "PA12_9") (pintype "passive"))
    )
    (net (code "184") (name "unconnected-(U1-PA15-Pad10)") (class "Default")
      (node (ref "U1") (pin "10") (pinfunction "PA15_10") (pintype "passive"))
    )
    (net (code "185") (name "unconnected-(U1-PB0-Pad33)") (class "Default")
      (node (ref "U1") (pin "33") (pinfunction "PB0_33") (pintype "passive"))
    )
    (net (code "186") (name "unconnected-(U1-PB1-Pad34)") (class "Default")
      (node (ref "U1") (pin "34") (pinfunction "PB1_34") (pintype "passive"))
    )
    (net (code "187") (name "unconnected-(U1-PB3-Pad11)") (class "Default")
      (node (ref "U1") (pin "11") (pinfunction "PB3_11") (pintype "passive"))
    )
    (net (code "188") (name "unconnected-(U1-PB4-Pad12)") (class "Default")
      (node (ref "U1") (pin "12") (pinfunction "PB4_12") (pintype "passive"))
    )
    (net (code "189") (name "unconnected-(U1-PB14-Pad3)") (class "Default")
      (node (ref "U1") (pin "3") (pinfunction "PB14_3") (pintype "passive"))
    )
    (net (code "190") (name "unconnected-(U1-PC13-Pad22)") (class "Default")
      (node (ref "U1") (pin "22") (pinfunction "PC13_22") (pintype "passive"))
    )
    (net (code "191") (name "unconnected-(U1-PC14-Pad23)") (class "Default")
      (node (ref "U1") (pin "23") (pinfunction "PC14_23") (pintype "passive"))
    )
    (net (code "192") (name "unconnected-(U1-PC15-Pad24)") (class "Default")
      (node (ref "U1") (pin "24") (pinfunction "PC15_24") (pintype "passive"))
    )
    (net (code "193") (name "unconnected-(U1-VBAT-Pad21)") (class "Default")
      (node (ref "U1") (pin "21") (pinfunction "VBAT_21") (pintype "passive"))
    )
    (net (code "194") (name "unconnected-(U4-3V3-Pad20)") (class "Default")
      (node (ref "U4") (pin "20") (pinfunction "3V3_20") (pintype "passive"))
    )
    (net (code "195") (name "unconnected-(U4-3V3-Pad38)") (class "Default")
      (node (ref "U4") (pin "38") (pinfunction "3V3_38") (pintype "passive"))
    )
    (net (code "196") (name "unconnected-(U4-GND-Pad19)") (class "Default")
      (node (ref "U4") (pin "19") (pinfunction "GND_19") (pintype "passive"))
    )
    (net (code "197") (name "unconnected-(U4-PA1-Pad26)") (class "Default")
      (node (ref "U4") (pin "26") (pinfunction "PA1_26") (pintype "passive"))
    )
    (net (code "198") (name "unconnected-(U4-PA2-Pad27)") (class "Default")
      (node (ref "U4") (pin "27") (pinfunction "PA2_27") (pintype "passive"))
    )
    (net (code "199") (name "unconnected-(U4-PA11-Pad8)") (class "Default")
      (node (ref "U4") (pin "8") (pinfunction "PA11_8") (pintype "passive"))
    )
    (net (code "200") (name "unconnected-(U4-PA12-Pad9)") (class "Default")
      (node (ref "U4") (pin "9") (pinfunction "PA12_9") (pintype "passive"))
    )
    (net (code "201") (name "unconnected-(U4-PA15-Pad10)") (class "Default")
      (node (ref "U4") (pin "10") (pinfunction "PA15_10") (pintype "passive"))
    )
    (net (code "202") (name "unconnected-(U4-PB0-Pad33)") (class "Default")
      (node (ref "U4") (pin "33") (pinfunction "PB0_33") (pintype "passive"))
    )
    (net (code "203") (name "unconnected-(U4-PB1-Pad34)") (class "Default")
      (node (ref "U4") (pin "34") (pinfunction "PB1_34") (pintype "passive"))
    )
    (net (code "204") (name "unconnected-(U4-PB3-Pad11)") (class "Default")
      (node (ref "U4") (pin "11") (pinfunction "PB3_11") (pintype "passive"))
    )
    (net (code "205") (name "unconnected-(U4-PB4-Pad12)") (class "Default")
      (node (ref "U4") (pin "12") (pinfunction "PB4_12") (pintype "passive"))
    )
    (net (code "206") (name "unconnected-(U4-PB5-Pad13)") (class "Default")
      (node (ref "U4") (pin "13") (pinfunction "PB5_13") (pintype "passive"))
    )
    (net (code "207") (name "unconnected-(U4-PB6-Pad14)") (class "Default")
      (node (ref "U4") (pin "14") (pinfunction "PB6_14") (pintype "passive"))
    )
    (net (code "208") (name "unconnected-(U4-PB7-Pad15)") (class "Default")
      (node (ref "U4") (pin "15") (pinfunction "PB7_15") (pintype "passive"))
    )
    (net (code "209") (name "unconnected-(U4-PB8-Pad16)") (class "Default")
      (node (ref "U4") (pin "16") (pinfunction "PB8_16") (pintype "passive"))
    )
    (net (code "210") (name "unconnected-(U4-PB9-Pad17)") (class "Default")
      (node (ref "U4") (pin "17") (pinfunction "PB9_17") (pintype "passive"))
    )
    (net (code "211") (name "unconnected-(U4-PB10-Pad35)") (class "Default")
      (node (ref "U4") (pin "35") (pinfunction "PB10_35") (pintype "passive"))
    )
    (net (code "212") (name "unconnected-(U4-PB11-Pad36)") (class "Default")
      (node (ref "U4") (pin "36") (pinfunction "PB11_36") (pintype "passive"))
    )
    (net (code "213") (name "unconnected-(U4-PB14-Pad3)") (class "Default")
      (node (ref "U4") (pin "3") (pinfunction "PB14_3") (pintype "passive"))
    )
    (net (code "214") (name "unconnected-(U4-PC13-Pad22)") (class "Default")
      (node (ref "U4") (pin "22") (pinfunction "PC13_22") (pintype "passive"))
    )
    (net (code "215") (name "unconnected-(U4-PC14-Pad23)") (class "Default")
      (node (ref "U4") (pin "23") (pinfunction "PC14_23") (pintype "passive"))
    )
    (net (code "216") (name "unconnected-(U4-PC15-Pad24)") (class "Default")
      (node (ref "U4") (pin "24") (pinfunction "PC15_24") (pintype "passive"))
    )
    (net (code "217") (name "unconnected-(U4-VBAT-Pad21)") (class "Default")
      (node (ref "U4") (pin "21") (pinfunction "VBAT_21") (pintype "passive"))
    )
    (net (code "218") (name "unconnected-(U6-3V3-Pad20)") (class "Default")
      (node (ref "U6") (pin "20") (pinfunction "3V3_20") (pintype "passive"))
    )
    (net (code "219") (name "unconnected-(U6-3V3-Pad38)") (class "Default")
      (node (ref "U6") (pin "38") (pinfunction "3V3_38") (pintype "passive"))
    )
    (net (code "220") (name "unconnected-(U6-GND-Pad19)") (class "Default")
      (node (ref "U6") (pin "19") (pinfunction "GND_19") (pintype "passive"))
    )
    (net (code "221") (name "unconnected-(U6-PA1-Pad26)") (class "Default")
      (node (ref "U6") (pin "26") (pinfunction "PA1_26") (pintype "passive"))
    )
    (net (code "222") (name "unconnected-(U6-PA2-Pad27)") (class "Default")
      (node (ref "U6") (pin "27") (pinfunction "PA2_27") (pintype "passive"))
    )
    (net (code "223") (name "unconnected-(U6-PA11-Pad8)") (class "Default")
      (node (ref "U6") (pin "8") (pinfunction "PA11_8") (pintype "passive"))
    )
    (net (code "224") (name "unconnected-(U6-PA12-Pad9)") (class "Default")
      (node (ref "U6") (pin "9") (pinfunction "PA12_9") (pintype "passive"))
    )
    (net (code "225") (name "unconnected-(U6-PA15-Pad10)") (class "Default")
      (node (ref "U6") (pin "10") (pinfunction "PA15_10") (pintype "passive"))
    )
    (net (code "226") (name "unconnected-(U6-PB0-Pad33)") (class "Default")
      (node (ref "U6") (pin "33") (pinfunction "PB0_33") (pintype "passive"))
    )
    (net (code "227") (name "unconnected-(U6-PB1-Pad34)") (class "Default")
      (node (ref "U6") (pin "34") (pinfunction "PB1_34") (pintype "passive"))
    )
    (net (code "228") (name "unconnected-(U6-PB3-Pad11)") (class "Default")
      (node (ref "U6") (pin "11") (pinfunction "PB3_11") (pintype "passive"))
    )
    (net (code "229") (name "unconnected-(U6-PB4-Pad12)") (class "Default")
      (node (ref "U6") (pin "12") (pinfunction "PB4_12") (pintype "passive"))
    )
    (net (code "230") (name "unconnected-(U6-PB5-Pad13)") (class "Default")
      (node (ref "U6") (pin "13") (pinfunction "PB5_13") (pintype "passive"))
    )
    (net (code "231") (name "unconnected-(U6-PB6-Pad14)") (class "Default")
      (node (ref "U6") (pin "14") (pinfunction "PB6_14") (pintype "passive"))
    )
    (net (code "232") (name "unconnected-(U6-PB7-Pad15)") (class "Default")
      (node (ref "U6") (pin "15") (pinfunction "PB7_15") (pintype "passive"))
    )
    (net (code "233") (name "unconnected-(U6-PB8-Pad16)") (class "Default")
      (node (ref "U6") (pin "16") (pinfunction "PB8_16") (pintype "passive"))
    )
    (net (code "234") (name "unconnected-(U6-PB9-Pad17)") (class "Default")
      (node (ref "U6") (pin "17") (pinfunction "PB9_17") (pintype "passive"))
    )
    (net (code "235") (name "unconnected-(U6-PB10-Pad35)") (class "Default")
      (node (ref "U6") (pin "35") (pinfunction "PB10_35") (pintype "passive"))
    )
    (net (code "236") (name "unconnected-(U6-PB11-Pad36)") (class "Default")
      (node (ref "U6") (pin "36") (pinfunction "PB11_36") (pintype "passive"))
    )
    (net (code "237") (name "unconnected-(U6-PB14-Pad3)") (class "Default")
      (node (ref "U6") (pin "3") (pinfunction "PB14_3") (pintype "passive"))
    )
    (net (code "238") (name "unconnected-(U6-PC13-Pad22)") (class "Default")
      (node (ref "U6") (pin "22") (pinfunction "PC13_22") (pintype "passive"))
    )
    (net (code "239") (name "unconnected-(U6-PC14-Pad23)") (class "Default")
      (node (ref "U6") (pin "23") (pinfunction "PC14_23") (pintype "passive"))
    )
    (net (code "240") (name "unconnected-(U6-PC15-Pad24)") (class "Default")
      (node (ref "U6") (pin "24") (pinfunction "PC15_24") (pintype "passive"))
    )
    (net (code "241") (name "unconnected-(U6-VBAT-Pad21)") (class "Default")
      (node (ref "U6") (pin "21") (pinfunction "VBAT_21") (pintype "passive"))
    )
    (net (code "242") (name "unconnected-(U8-3V3-Pad20)") (class "Default")
      (node (ref "U8") (pin "20") (pinfunction "3V3_20") (pintype "passive"))
    )
    (net (code "243") (name "unconnected-(U8-3V3-Pad38)") (class "Default")
      (node (ref "U8") (pin "38") (pinfunction "3V3_38") (pintype "passive"))
    )
    (net (code "244") (name "unconnected-(U8-GND-Pad19)") (class "Default")
      (node (ref "U8") (pin "19") (pinfunction "GND_19") (pintype "passive"))
    )
    (net (code "245") (name "unconnected-(U8-PA1-Pad26)") (class "Default")
      (node (ref "U8") (pin "26") (pinfunction "PA1_26") (pintype "passive"))
    )
    (net (code "246") (name "unconnected-(U8-PA2-Pad27)") (class "Default")
      (node (ref "U8") (pin "27") (pinfunction "PA2_27") (pintype "passive"))
    )
    (net (code "247") (name "unconnected-(U8-PA11-Pad8)") (class "Default")
      (node (ref "U8") (pin "8") (pinfunction "PA11_8") (pintype "passive"))
    )
    (net (code "248") (name "unconnected-(U8-PA12-Pad9)") (class "Default")
      (node (ref "U8") (pin "9") (pinfunction "PA12_9") (pintype "passive"))
    )
    (net (code "249") (name "unconnected-(U8-PA15-Pad10)") (class "Default")
      (node (ref "U8") (pin "10") (pinfunction "PA15_10") (pintype "passive"))
    )
    (net (code "250") (name "unconnected-(U8-PB0-Pad33)") (class "Default")
      (node (ref "U8") (pin "33") (pinfunction "PB0_33") (pintype "passive"))
    )
    (net (code "251") (name "unconnected-(U8-PB1-Pad34)") (class "Default")
      (node (ref "U8") (pin "34") (pinfunction "PB1_34") (pintype "passive"))
    )
    (net (code "252") (name "unconnected-(U8-PB3-Pad11)") (class "Default")
      (node (ref "U8") (pin "11") (pinfunction "PB3_11") (pintype "passive"))
    )
    (net (code "253") (name "unconnected-(U8-PB4-Pad12)") (class "Default")
      (node (ref "U8") (pin "12") (pinfunction "PB4_12") (pintype "passive"))
    )
    (net (code "254") (name "unconnected-(U8-PB5-Pad13)") (class "Default")
      (node (ref "U8") (pin "13") (pinfunction "PB5_13") (pintype "passive"))
    )
    (net (code "255") (name "unconnected-(U8-PB6-Pad14)") (class "Default")
      (node (ref "U8") (pin "14") (pinfunction "PB6_14") (pintype "passive"))
    )
    (net (code "256") (name "unconnected-(U8-PB7-Pad15)") (class "Default")
      (node (ref "U8") (pin "15") (pinfunction "PB7_15") (pintype "passive"))
    )
    (net (code "257") (name "unconnected-(U8-PB8-Pad16)") (class "Default")
      (node (ref "U8") (pin "16") (pinfunction "PB8_16") (pintype "passive"))
    )
    (net (code "258") (name "unconnected-(U8-PB9-Pad17)") (class "Default")
      (node (ref "U8") (pin "17") (pinfunction "PB9_17") (pintype "passive"))
    )
    (net (code "259") (name "unconnected-(U8-PB10-Pad35)") (class "Default")
      (node (ref "U8") (pin "35") (pinfunction "PB10_35") (pintype "passive"))
    )
    (net (code "260") (name "unconnected-(U8-PB11-Pad36)") (class "Default")
      (node (ref "U8") (pin "36") (pinfunction "PB11_36") (pintype "passive"))
    )
    (net (code "261") (name "unconnected-(U8-PB14-Pad3)") (class "Default")
      (node (ref "U8") (pin "3") (pinfunction "PB14_3") (pintype "passive"))
    )
    (net (code "262") (name "unconnected-(U8-PC13-Pad22)") (class "Default")
      (node (ref "U8") (pin "22") (pinfunction "PC13_22") (pintype "passive"))
    )
    (net (code "263") (name "unconnected-(U8-PC14-Pad23)") (class "Default")
      (node (ref "U8") (pin "23") (pinfunction "PC14_23") (pintype "passive"))
    )
    (net (code "264") (name "unconnected-(U8-PC15-Pad24)") (class "Default")
      (node (ref "U8") (pin "24") (pinfunction "PC15_24") (pintype "passive"))
    )
    (net (code "265") (name "unconnected-(U8-VBAT-Pad21)") (class "Default")
      (node (ref "U8") (pin "21") (pinfunction "VBAT_21") (pintype "passive"))
    )
  )
)
